# BMS_Master.net
KiCad netlist of a schematic drawn in EAGLE
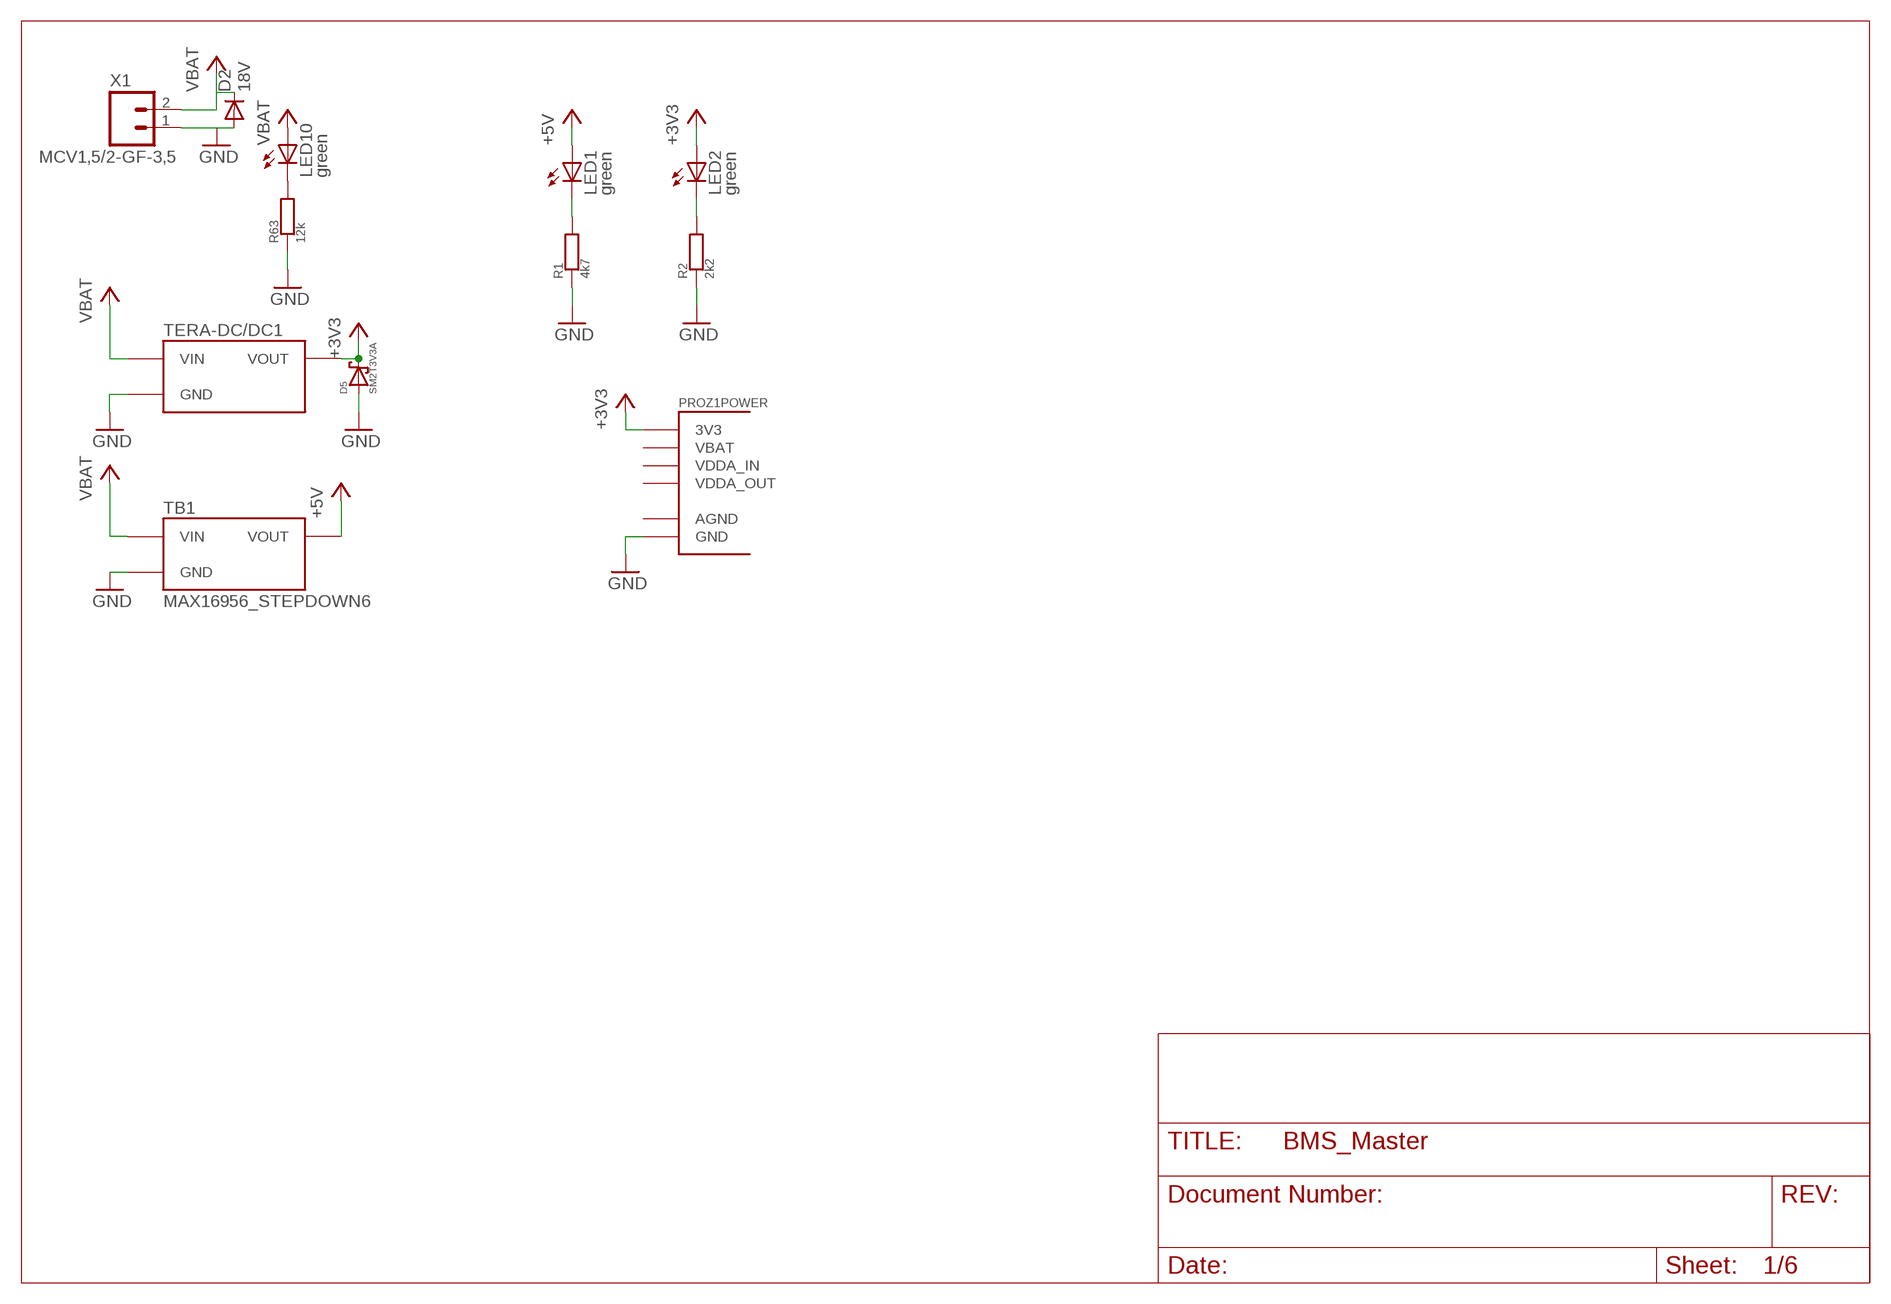
[diagram p0: schematic, sheet 1]
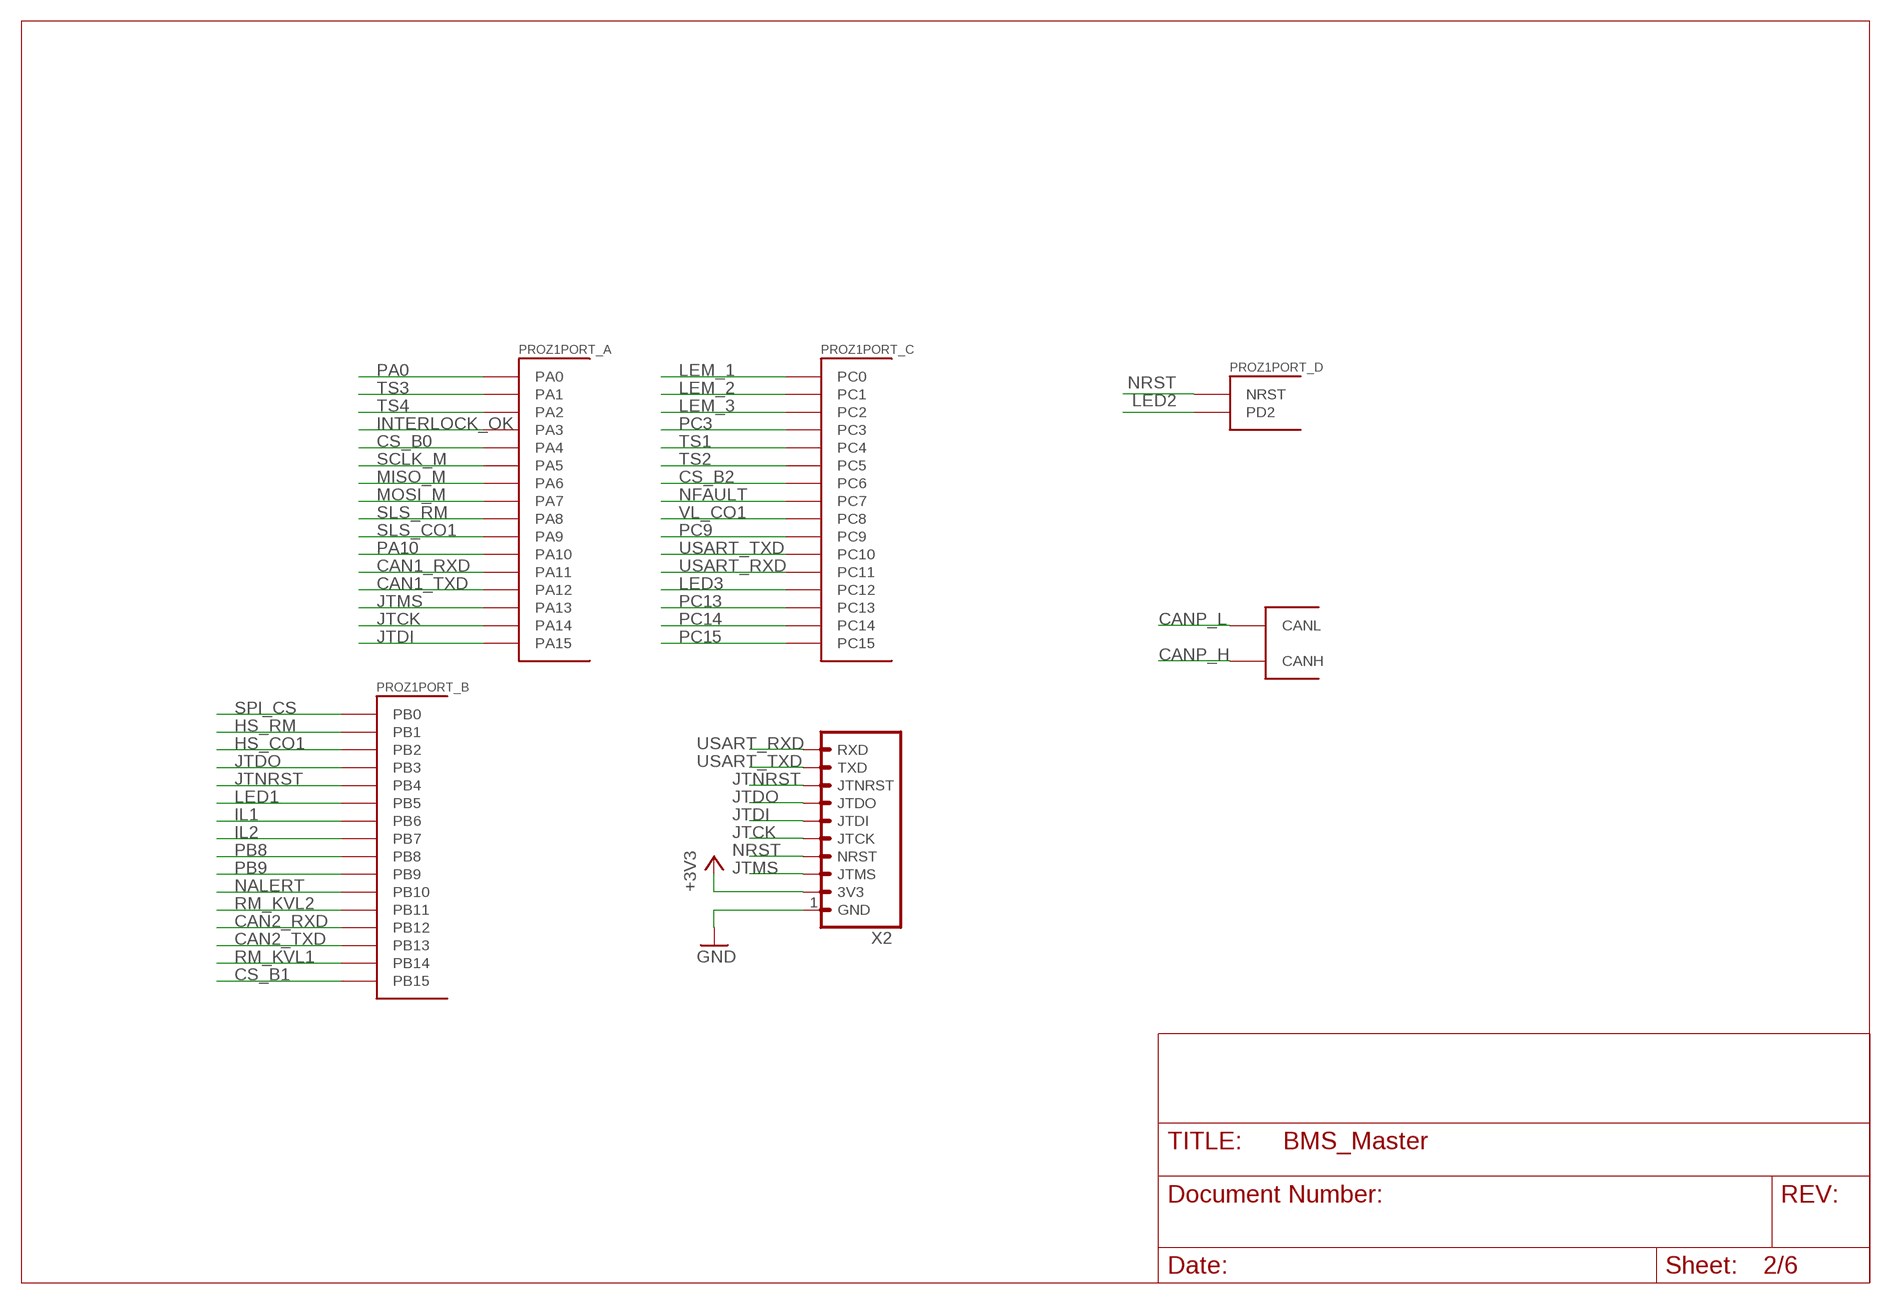
[diagram p1: schematic, sheet 2]
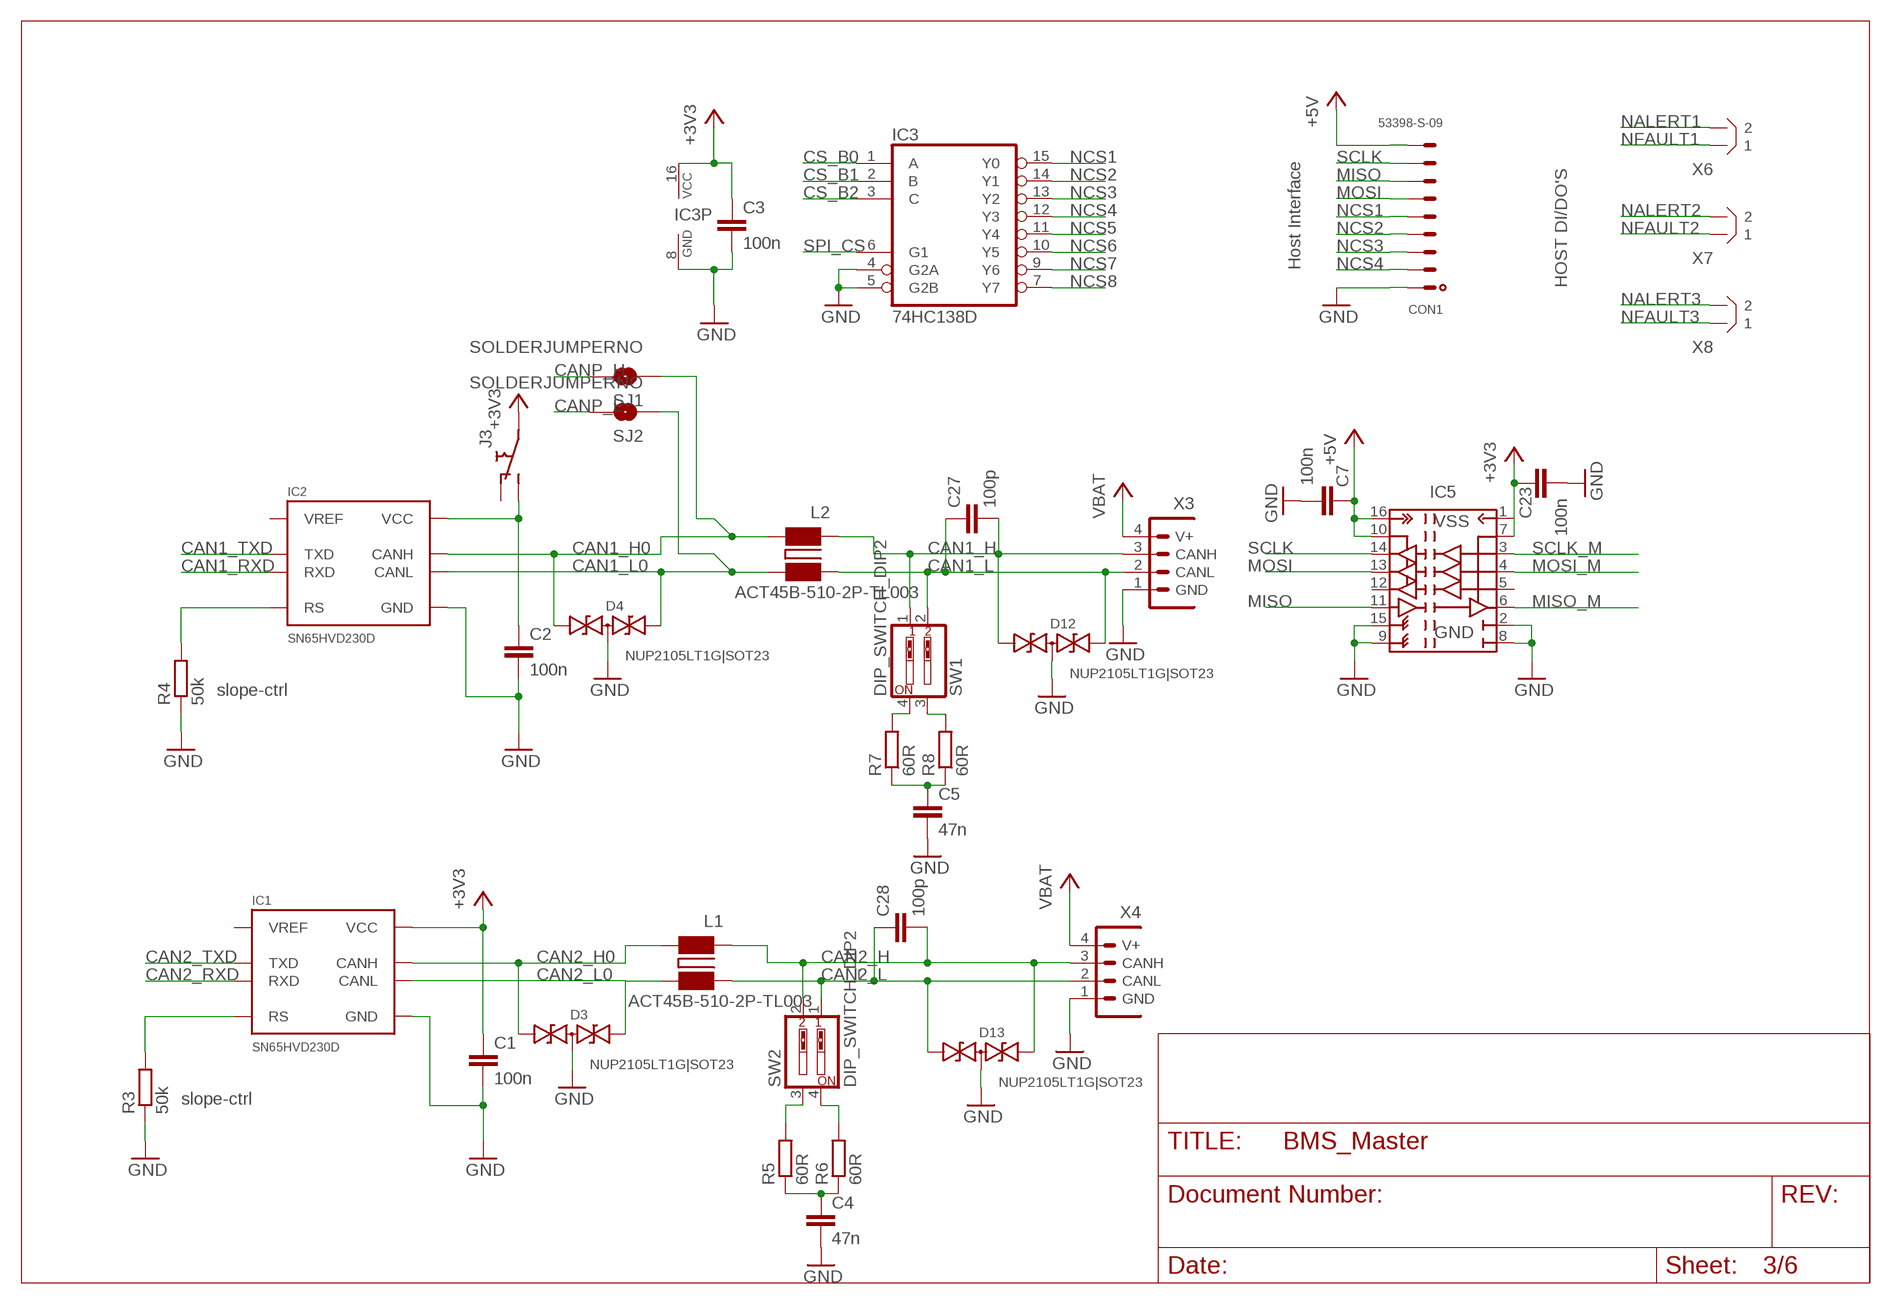
[diagram p2: schematic, sheet 3]
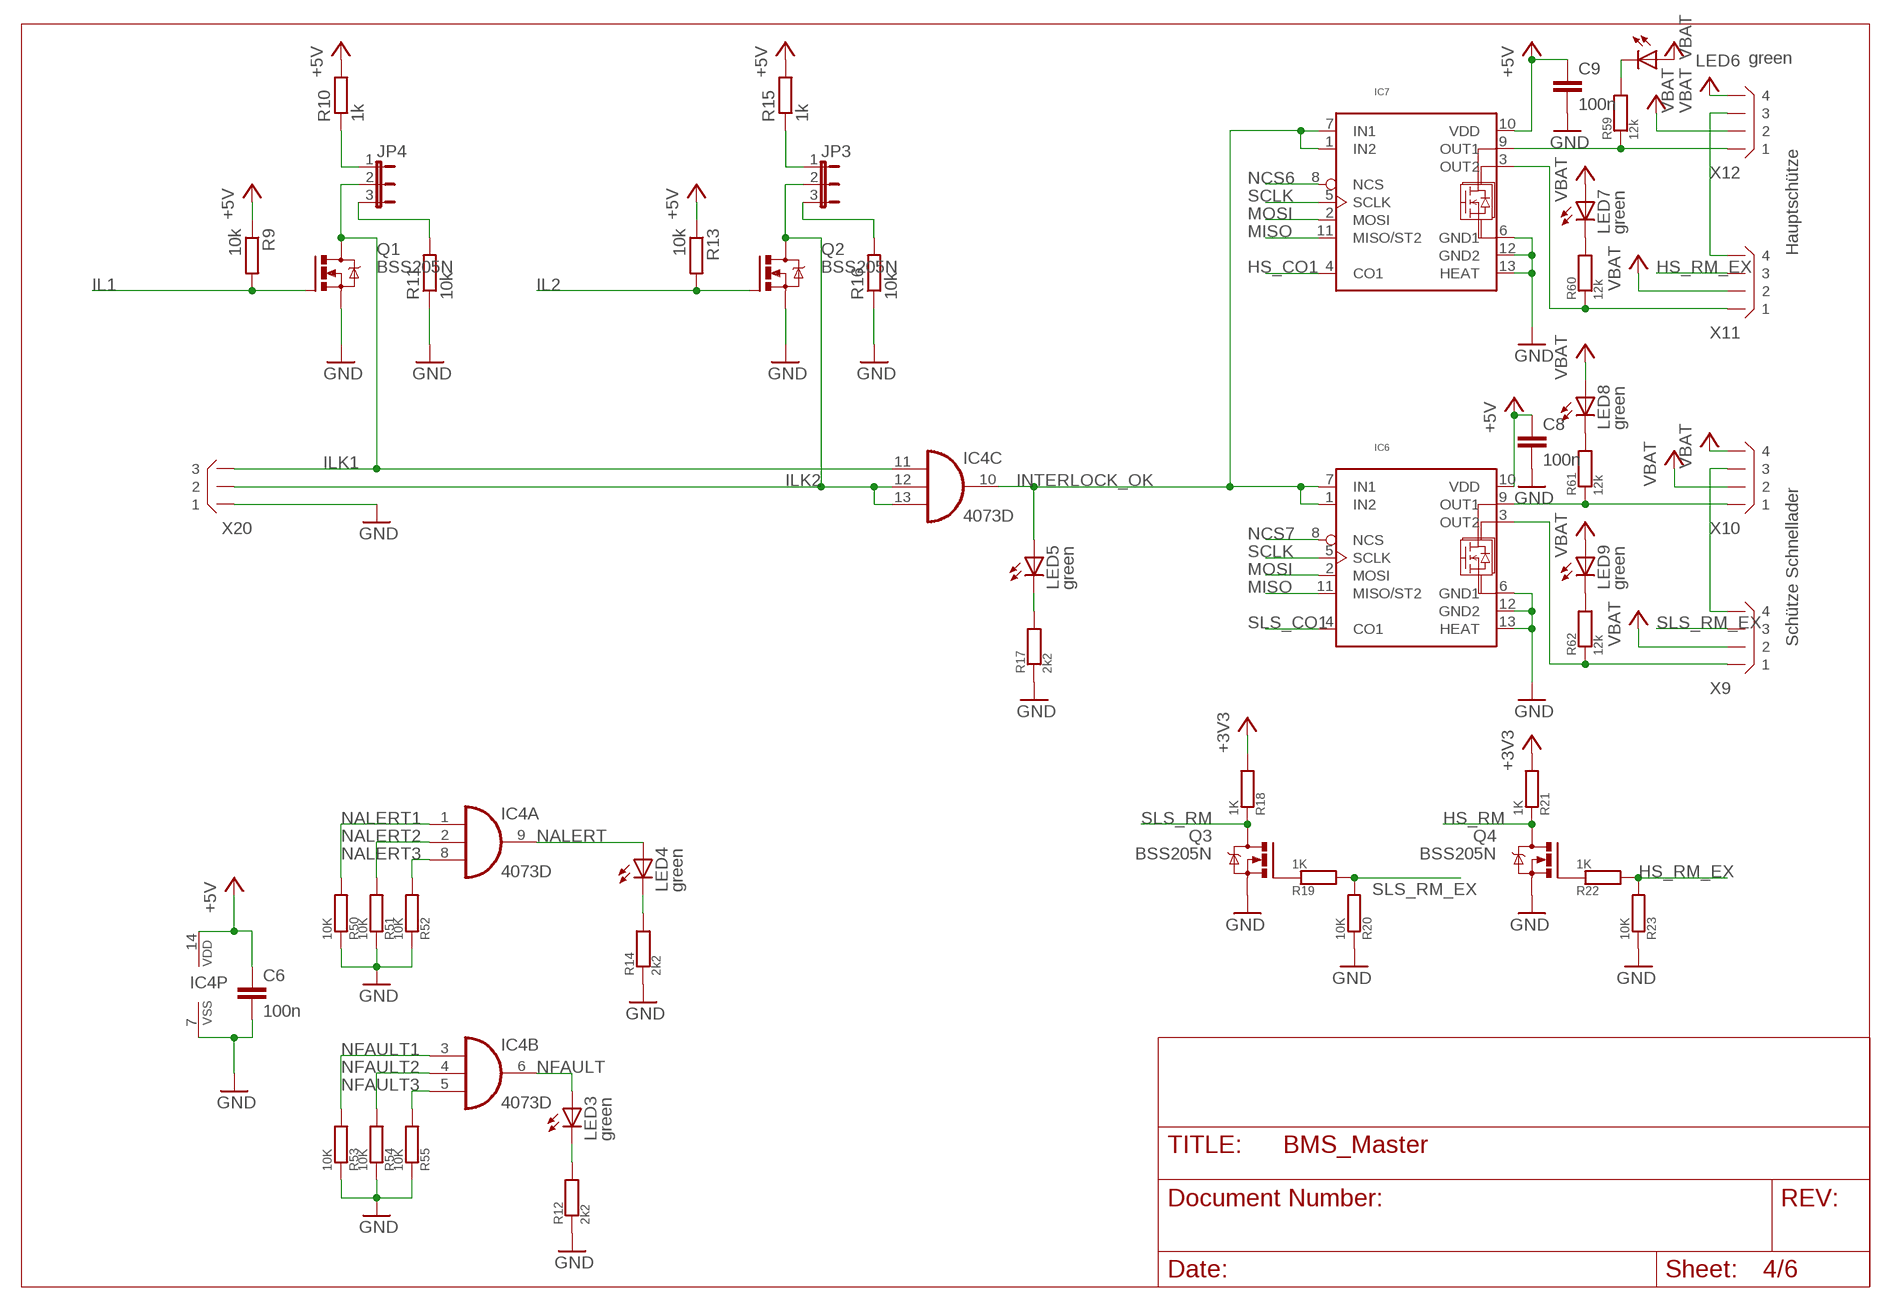
[diagram p3: schematic, sheet 4]
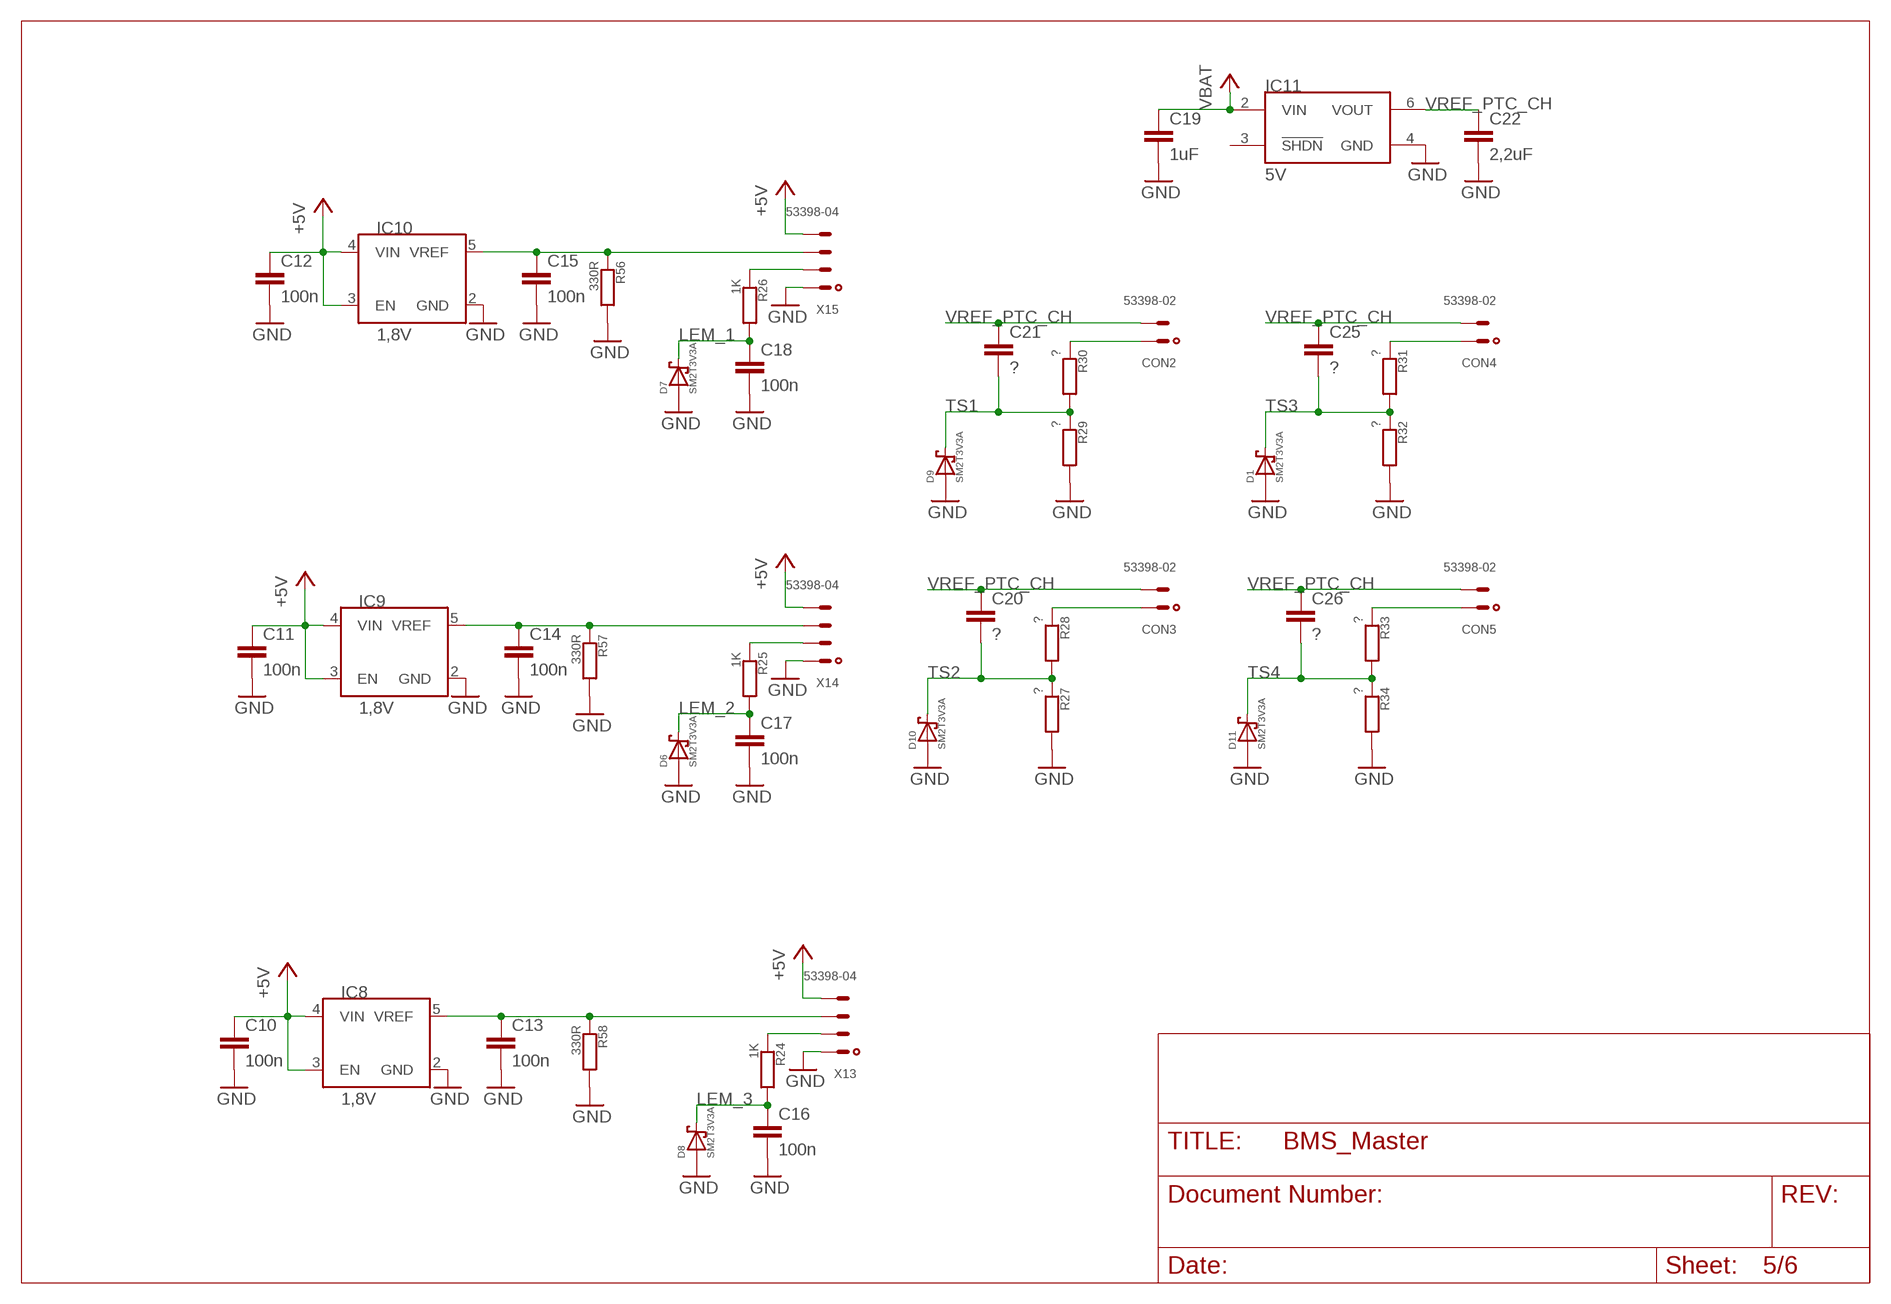
[diagram p4: schematic, sheet 5]
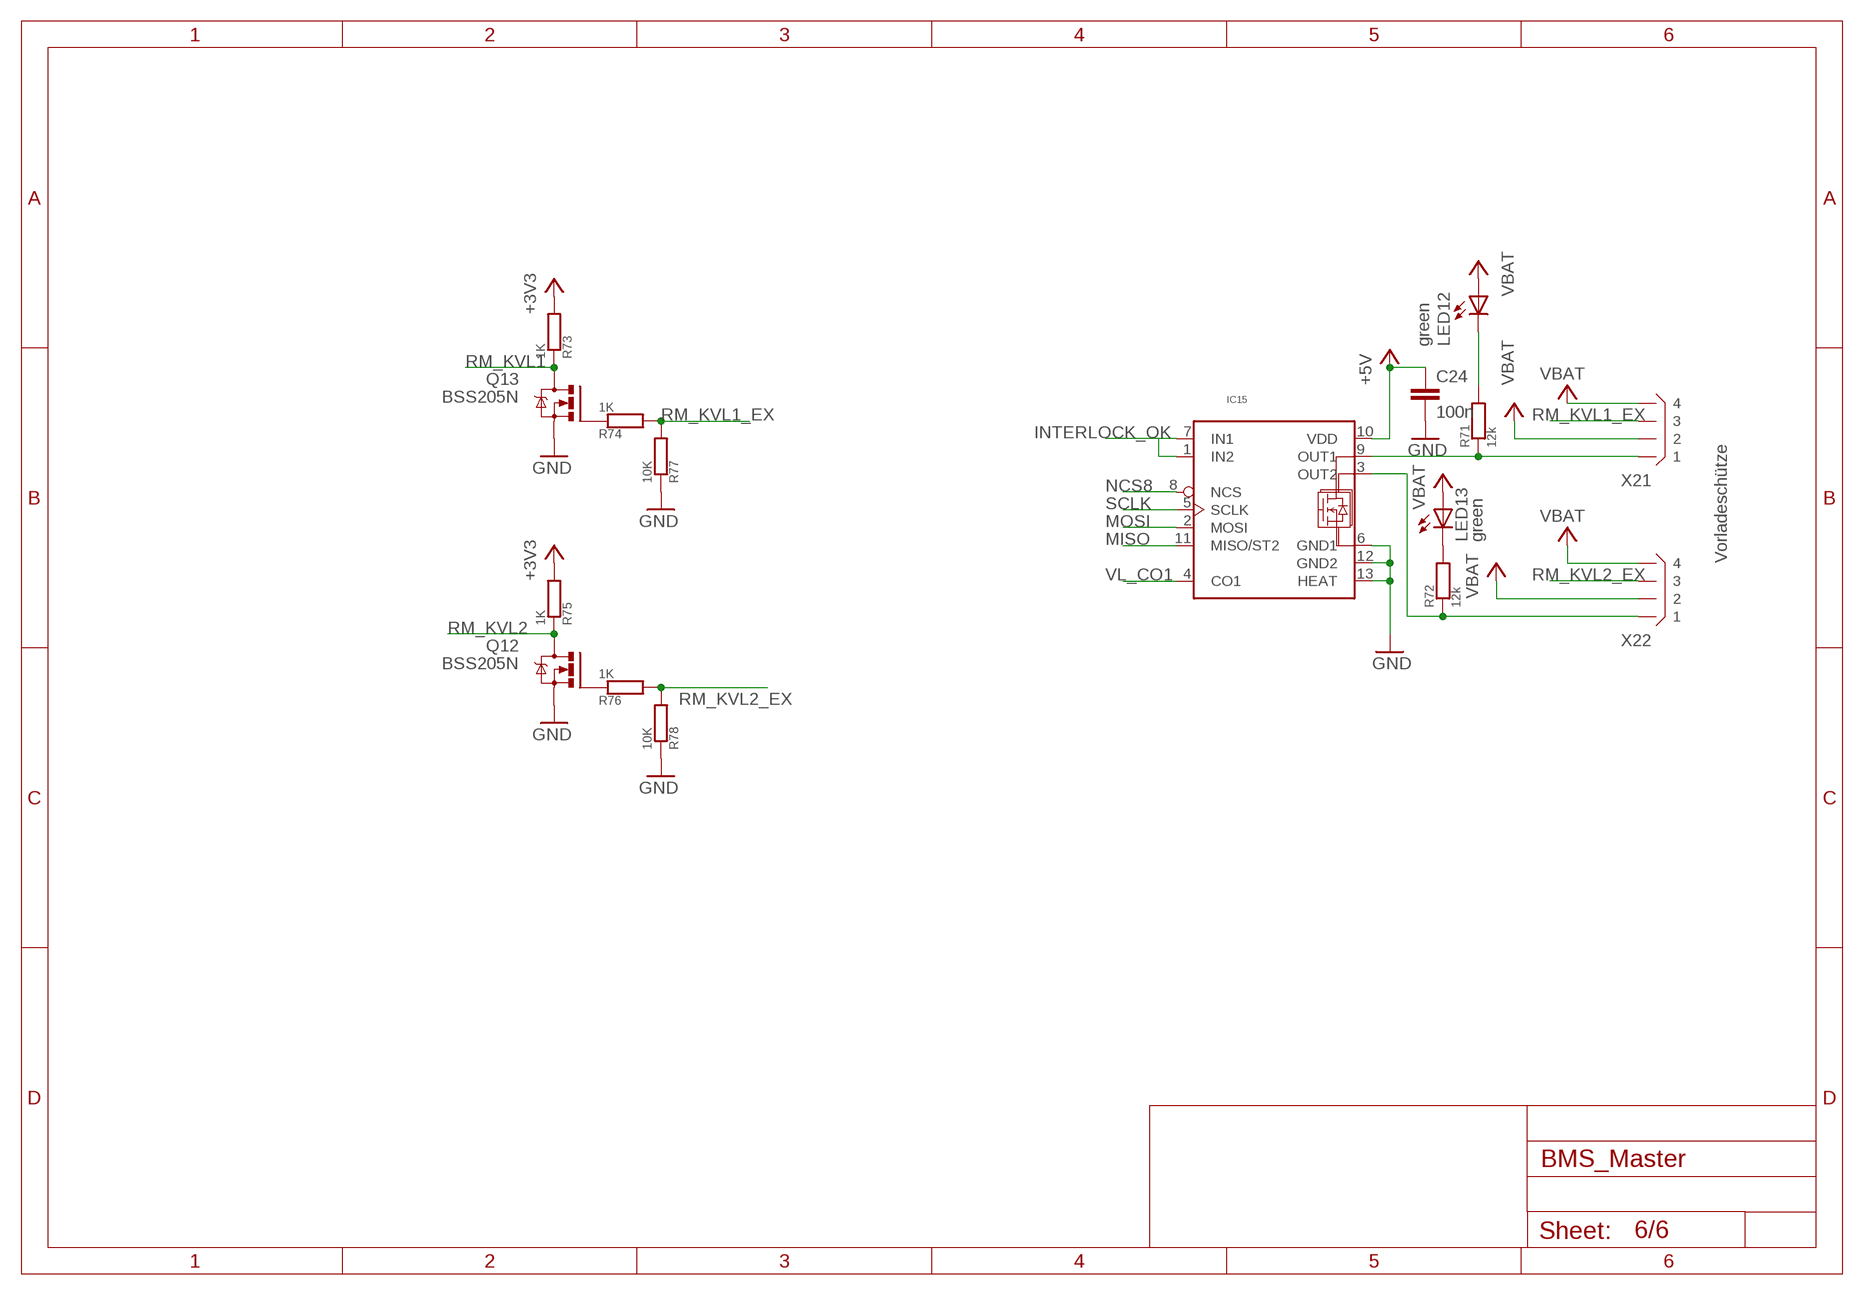
[diagram p5: schematic, sheet 6]

(export (version "E")
  (design (tool "Eeschema 10.0.6"))
  (components
    (comp (ref "PROZ1")
      (value "STM32F4_PROZESSORBOARDRPZ")
      (footprint "eagle-import:STM32F4_PROZESSORBOARD")
      (libsource (lib "eagle-import") (part "STM32F4_PROZESSORBOARDRPZ"))
    )
    (comp (ref "X2")
      (value "TERA-PROG-DEBUG-10GERADE")
      (footprint "eagle-import:90130-1110")
      (libsource (lib "eagle-import") (part "TERA-PROG-DEBUG-10GERADE"))
    )
    (comp (ref "D2")
      (value "18V")
      (footprint "eagle-import:DO214AA")
      (libsource (lib "eagle-import") (part "DIODE-DO214AA"))
    )
    (comp (ref "D5")
      (value "SM2T3V3A")
      (footprint "eagle-import:SM2T3V3A")
      (libsource (lib "eagle-import") (part "SM2T3V3A"))
    )
    (comp (ref "LED1")
      (value "green")
      (footprint "eagle-import:CHIP-LED0805")
      (libsource (lib "eagle-import") (part "LEDCHIP-LED0805"))
    )
    (comp (ref "LED2")
      (value "green")
      (footprint "eagle-import:CHIP-LED0805")
      (libsource (lib "eagle-import") (part "LEDCHIP-LED0805"))
    )
    (comp (ref "LED10")
      (value "green")
      (footprint "eagle-import:CHIP-LED0805")
      (libsource (lib "eagle-import") (part "LEDCHIP-LED0805"))
    )
    (comp (ref "R1")
      (value "4k7")
      (footprint "eagle-import:R0805")
      (libsource (lib "eagle-import") (part "R"))
    )
    (comp (ref "R2")
      (value "2k2")
      (footprint "eagle-import:R0805")
      (libsource (lib "eagle-import") (part "R"))
    )
    (comp (ref "R63")
      (value "12k")
      (footprint "eagle-import:R0805")
      (libsource (lib "eagle-import") (part "R"))
    )
    (comp (ref "TB1")
      (value "MAX16956_STEPDOWN6")
      (footprint "eagle-import:MAX16956_STEPDOWN6")
      (libsource (lib "eagle-import") (part "MAX16956_STEPDOWN6"))
    )
    (comp (ref "TERA-DC/DC1")
      (value "MAX5035_STEPDOWN3")
      (footprint "eagle-import:MAX5035_STEPDOWN3")
      (libsource (lib "eagle-import") (part "MAX5035_STEPDOWN3"))
    )
    (comp (ref "X1")
      (value "MCV1,5/2-GF-3,5")
      (footprint "eagle-import:MCV1,5_2-GF-3,5")
      (libsource (lib "eagle-import") (part "MCV1,5/2-GF-3,5"))
    )
    (comp (ref "C1")
      (value "100n")
      (footprint "eagle-import:C0805")
      (libsource (lib "eagle-import") (part "C-EUC0805"))
    )
    (comp (ref "C2")
      (value "100n")
      (footprint "eagle-import:C0805")
      (libsource (lib "eagle-import") (part "C-EUC0805"))
    )
    (comp (ref "C3")
      (value "100n")
      (footprint "eagle-import:C0805")
      (libsource (lib "eagle-import") (part "C-EUC0805"))
    )
    (comp (ref "C4")
      (value "47n")
      (footprint "eagle-import:C0603")
      (libsource (lib "eagle-import") (part "C-EUC0603"))
    )
    (comp (ref "C5")
      (value "47n")
      (footprint "eagle-import:C0603")
      (libsource (lib "eagle-import") (part "C-EUC0603"))
    )
    (comp (ref "C7")
      (value "100n")
      (footprint "eagle-import:C0603")
      (libsource (lib "eagle-import") (part "C0603"))
    )
    (comp (ref "C23")
      (value "100n")
      (footprint "eagle-import:C0603")
      (libsource (lib "eagle-import") (part "C0603"))
    )
    (comp (ref "C27")
      (value "100p")
      (footprint "eagle-import:C0603")
      (libsource (lib "eagle-import") (part "C-EUC0603"))
    )
    (comp (ref "C28")
      (value "100p")
      (footprint "eagle-import:C0603")
      (libsource (lib "eagle-import") (part "C-EUC0603"))
    )
    (comp (ref "CON1")
      (value "53398-S-09")
      (footprint "eagle-import:53398-09-S")
      (libsource (lib "eagle-import") (part "53?-09398-S"))
    )
    (comp (ref "D3")
      (value "NUP2105LT1G|SOT23")
      (footprint "eagle-import:SOT23")
      (libsource (lib "eagle-import") (part "NUP2105LT1G|SOT23"))
    )
    (comp (ref "D4")
      (value "NUP2105LT1G|SOT23")
      (footprint "eagle-import:SOT23")
      (libsource (lib "eagle-import") (part "NUP2105LT1G|SOT23"))
    )
    (comp (ref "D12")
      (value "NUP2105LT1G|SOT23")
      (footprint "eagle-import:SOT23")
      (libsource (lib "eagle-import") (part "NUP2105LT1G|SOT23"))
    )
    (comp (ref "D13")
      (value "NUP2105LT1G|SOT23")
      (footprint "eagle-import:SOT23")
      (libsource (lib "eagle-import") (part "NUP2105LT1G|SOT23"))
    )
    (comp (ref "IC1")
      (value "SN65HVD230D")
      (footprint "eagle-import:SO08")
      (libsource (lib "eagle-import") (part "SN65HVD23D0"))
    )
    (comp (ref "IC2")
      (value "SN65HVD230D")
      (footprint "eagle-import:SO08")
      (libsource (lib "eagle-import") (part "SN65HVD23D0"))
    )
    (comp (ref "IC3")
      (value "74HC138D")
      (footprint "eagle-import:SO16")
      (libsource (lib "eagle-import") (part "74138DHC"))
    )
    (comp (ref "IC5")
      (value "ISO7241")
      (footprint "eagle-import:R-PDSO-G16")
      (libsource (lib "eagle-import") (part "ISO7241"))
    )
    (comp (ref "J3")
      (value "JUMPER_SWITCHS")
      (footprint "eagle-import:J_OR_S")
      (libsource (lib "eagle-import") (part "JUMPER_SWITCHS"))
    )
    (comp (ref "L1")
      (value "ACT45B-510-2P-TL003")
      (footprint "eagle-import:ACT45B")
      (libsource (lib "eagle-import") (part "ACT45B-510-2P-TL003"))
    )
    (comp (ref "L2")
      (value "ACT45B-510-2P-TL003")
      (footprint "eagle-import:ACT45B")
      (libsource (lib "eagle-import") (part "ACT45B-510-2P-TL003"))
    )
    (comp (ref "R3")
      (value "50k")
      (footprint "eagle-import:R0805")
      (libsource (lib "eagle-import") (part "R-EU_R0805"))
    )
    (comp (ref "R4")
      (value "50k")
      (footprint "eagle-import:R0805")
      (libsource (lib "eagle-import") (part "R-EU_R0805"))
    )
    (comp (ref "R5")
      (value "60R")
      (footprint "eagle-import:R0603")
      (libsource (lib "eagle-import") (part "R-EU_R0603"))
    )
    (comp (ref "R6")
      (value "60R")
      (footprint "eagle-import:R0603")
      (libsource (lib "eagle-import") (part "R-EU_R0603"))
    )
    (comp (ref "R7")
      (value "60R")
      (footprint "eagle-import:R0603")
      (libsource (lib "eagle-import") (part "R-EU_R0603"))
    )
    (comp (ref "R8")
      (value "60R")
      (footprint "eagle-import:R0603")
      (libsource (lib "eagle-import") (part "R-EU_R0603"))
    )
    (comp (ref "SJ1")
      (value "SOLDERJUMPERNO")
      (footprint "eagle-import:SJ_2S-NO")
      (libsource (lib "eagle-import") (part "SOLDERJUMPERNO"))
    )
    (comp (ref "SJ2")
      (value "SOLDERJUMPERNO")
      (footprint "eagle-import:SJ_2S-NO")
      (libsource (lib "eagle-import") (part "SOLDERJUMPERNO"))
    )
    (comp (ref "SW1")
      (value "DIP_SWITCH_DIP2")
      (footprint "eagle-import:DIPSWITCH-02")
      (libsource (lib "eagle-import") (part "DIP_SWITCH_DIP2"))
    )
    (comp (ref "SW2")
      (value "DIP_SWITCH_DIP2")
      (footprint "eagle-import:DIPSWITCH-02")
      (libsource (lib "eagle-import") (part "DIP_SWITCH_DIP2"))
    )
    (comp (ref "X3")
      (value "CIOC_4-1-FV-A_CAN-BELEGUNG")
      (footprint "eagle-import:CIOC_4-1-FV")
      (libsource (lib "eagle-import") (part "CIOC_4-1-FV-A_CAN-BELEGUNG"))
    )
    (comp (ref "X4")
      (value "CIOC_4-1-FV-A_CAN-BELEGUNG")
      (footprint "eagle-import:CIOC_4-1-FV")
      (libsource (lib "eagle-import") (part "CIOC_4-1-FV-A_CAN-BELEGUNG"))
    )
    (comp (ref "X6")
      (value "B2B-XH")
      (footprint "eagle-import:B2B-XH")
      (libsource (lib "eagle-import") (part "?2B-XHB"))
    )
    (comp (ref "X7")
      (value "B2B-XH")
      (footprint "eagle-import:B2B-XH")
      (libsource (lib "eagle-import") (part "?2B-XHB"))
    )
    (comp (ref "X8")
      (value "B2B-XH")
      (footprint "eagle-import:B2B-XH")
      (libsource (lib "eagle-import") (part "?2B-XHB"))
    )
    (comp (ref "C6")
      (value "100n")
      (footprint "eagle-import:C0603")
      (libsource (lib "eagle-import") (part "C-EUC0603"))
    )
    (comp (ref "C8")
      (value "100n")
      (footprint "eagle-import:C0603")
      (libsource (lib "eagle-import") (part "C-EUC0603"))
    )
    (comp (ref "C9")
      (value "100n")
      (footprint "eagle-import:C0603")
      (libsource (lib "eagle-import") (part "C-EUC0603"))
    )
    (comp (ref "IC4")
      (value "4073D")
      (footprint "eagle-import:SO14")
      (libsource (lib "eagle-import") (part "4073D"))
    )
    (comp (ref "IC6")
      (value "TLE8102SGN")
      (footprint "eagle-import:INF-PG-DSO-12-11_N_1PRIMARY")
      (libsource (lib "eagle-import") (part "TLE8102SGN"))
    )
    (comp (ref "IC7")
      (value "TLE8102SGN")
      (footprint "eagle-import:INF-PG-DSO-12-11_N_1PRIMARY")
      (libsource (lib "eagle-import") (part "TLE8102SGN"))
    )
    (comp (ref "JP3")
      (value "JUMPER_OR")
      (footprint "eagle-import:JP2_OCT")
      (libsource (lib "eagle-import") (part "JUMPER_OR"))
    )
    (comp (ref "JP4")
      (value "JUMPER_OR")
      (footprint "eagle-import:JP2_OCT")
      (libsource (lib "eagle-import") (part "JUMPER_OR"))
    )
    (comp (ref "LED3")
      (value "green")
      (footprint "eagle-import:CHIPLED_0805")
      (libsource (lib "eagle-import") (part "LEDCHIPLED_0805"))
    )
    (comp (ref "LED4")
      (value "green")
      (footprint "eagle-import:CHIPLED_0805")
      (libsource (lib "eagle-import") (part "LEDCHIPLED_0805"))
    )
    (comp (ref "LED5")
      (value "green")
      (footprint "eagle-import:CHIPLED_0805")
      (libsource (lib "eagle-import") (part "LEDCHIPLED_0805"))
    )
    (comp (ref "LED6")
      (value "green")
      (footprint "eagle-import:CHIP-LED0805")
      (libsource (lib "eagle-import") (part "LEDCHIP-LED0805"))
    )
    (comp (ref "LED7")
      (value "green")
      (footprint "eagle-import:CHIP-LED0805")
      (libsource (lib "eagle-import") (part "LEDCHIP-LED0805"))
    )
    (comp (ref "LED8")
      (value "green")
      (footprint "eagle-import:CHIP-LED0805")
      (libsource (lib "eagle-import") (part "LEDCHIP-LED0805"))
    )
    (comp (ref "LED9")
      (value "green")
      (footprint "eagle-import:CHIP-LED0805")
      (libsource (lib "eagle-import") (part "LEDCHIP-LED0805"))
    )
    (comp (ref "Q1")
      (value "BSS205N")
      (footprint "eagle-import:SOT23")
      (libsource (lib "eagle-import") (part "BSS205N"))
    )
    (comp (ref "Q2")
      (value "BSS205N")
      (footprint "eagle-import:SOT23")
      (libsource (lib "eagle-import") (part "BSS205N"))
    )
    (comp (ref "Q3")
      (value "BSS205N")
      (footprint "eagle-import:SOT23")
      (libsource (lib "eagle-import") (part "BSS205N"))
    )
    (comp (ref "Q4")
      (value "BSS205N")
      (footprint "eagle-import:SOT23")
      (libsource (lib "eagle-import") (part "BSS205N"))
    )
    (comp (ref "R9")
      (value "10k")
      (footprint "eagle-import:R0603")
      (libsource (lib "eagle-import") (part "R-EU_R0603"))
    )
    (comp (ref "R10")
      (value "1k")
      (footprint "eagle-import:R0603")
      (libsource (lib "eagle-import") (part "R-EU_R0603"))
    )
    (comp (ref "R11")
      (value "10k")
      (footprint "eagle-import:R0603")
      (libsource (lib "eagle-import") (part "R-EU_R0603"))
    )
    (comp (ref "R12")
      (value "2k2")
      (footprint "eagle-import:R0805")
      (libsource (lib "eagle-import") (part "R"))
    )
    (comp (ref "R13")
      (value "10k")
      (footprint "eagle-import:R0603")
      (libsource (lib "eagle-import") (part "R-EU_R0603"))
    )
    (comp (ref "R14")
      (value "2k2")
      (footprint "eagle-import:R0805")
      (libsource (lib "eagle-import") (part "R"))
    )
    (comp (ref "R15")
      (value "1k")
      (footprint "eagle-import:R0603")
      (libsource (lib "eagle-import") (part "R-EU_R0603"))
    )
    (comp (ref "R16")
      (value "10k")
      (footprint "eagle-import:R0603")
      (libsource (lib "eagle-import") (part "R-EU_R0603"))
    )
    (comp (ref "R17")
      (value "2k2")
      (footprint "eagle-import:R0805")
      (libsource (lib "eagle-import") (part "R"))
    )
    (comp (ref "R18")
      (value "1K")
      (footprint "eagle-import:R0603")
      (libsource (lib "eagle-import") (part "R0603"))
    )
    (comp (ref "R19")
      (value "1K")
      (footprint "eagle-import:R0805")
      (libsource (lib "eagle-import") (part "R"))
    )
    (comp (ref "R20")
      (value "10K")
      (footprint "eagle-import:R0805")
      (libsource (lib "eagle-import") (part "R"))
    )
    (comp (ref "R21")
      (value "1K")
      (footprint "eagle-import:R0603")
      (libsource (lib "eagle-import") (part "R0603"))
    )
    (comp (ref "R22")
      (value "1K")
      (footprint "eagle-import:R0805")
      (libsource (lib "eagle-import") (part "R"))
    )
    (comp (ref "R23")
      (value "10K")
      (footprint "eagle-import:R0805")
      (libsource (lib "eagle-import") (part "R"))
    )
    (comp (ref "R50")
      (value "10K")
      (footprint "eagle-import:R0603")
      (libsource (lib "eagle-import") (part "R0603"))
    )
    (comp (ref "R51")
      (value "10K")
      (footprint "eagle-import:R0603")
      (libsource (lib "eagle-import") (part "R0603"))
    )
    (comp (ref "R52")
      (value "10K")
      (footprint "eagle-import:R0603")
      (libsource (lib "eagle-import") (part "R0603"))
    )
    (comp (ref "R53")
      (value "10K")
      (footprint "eagle-import:R0603")
      (libsource (lib "eagle-import") (part "R0603"))
    )
    (comp (ref "R54")
      (value "10K")
      (footprint "eagle-import:R0603")
      (libsource (lib "eagle-import") (part "R0603"))
    )
    (comp (ref "R55")
      (value "10K")
      (footprint "eagle-import:R0603")
      (libsource (lib "eagle-import") (part "R0603"))
    )
    (comp (ref "R59")
      (value "12k")
      (footprint "eagle-import:R0805")
      (libsource (lib "eagle-import") (part "R"))
    )
    (comp (ref "R60")
      (value "12k")
      (footprint "eagle-import:R0805")
      (libsource (lib "eagle-import") (part "R"))
    )
    (comp (ref "R61")
      (value "12k")
      (footprint "eagle-import:R0805")
      (libsource (lib "eagle-import") (part "R"))
    )
    (comp (ref "R62")
      (value "12k")
      (footprint "eagle-import:R0805")
      (libsource (lib "eagle-import") (part "R"))
    )
    (comp (ref "X9")
      (value "B4B-XH")
      (footprint "eagle-import:B4B-XH")
      (libsource (lib "eagle-import") (part "?4B-XHB"))
    )
    (comp (ref "X10")
      (value "B4B-XH")
      (footprint "eagle-import:B4B-XH")
      (libsource (lib "eagle-import") (part "?4B-XHB"))
    )
    (comp (ref "X11")
      (value "B4B-XH")
      (footprint "eagle-import:B4B-XH")
      (libsource (lib "eagle-import") (part "?4B-XHB"))
    )
    (comp (ref "X12")
      (value "B4B-XH")
      (footprint "eagle-import:B4B-XH")
      (libsource (lib "eagle-import") (part "?4B-XHB"))
    )
    (comp (ref "X20")
      (value "B3B-XH")
      (footprint "eagle-import:B3B-XH")
      (libsource (lib "eagle-import") (part "?3B-XHB"))
    )
    (comp (ref "C24")
      (value "100n")
      (footprint "eagle-import:C0603")
      (libsource (lib "eagle-import") (part "C-EUC0603"))
    )
    (comp (ref "IC15")
      (value "TLE8102SGN")
      (footprint "eagle-import:INF-PG-DSO-12-11_N_1PRIMARY")
      (libsource (lib "eagle-import") (part "TLE8102SGN"))
    )
    (comp (ref "LED12")
      (value "green")
      (footprint "eagle-import:CHIP-LED0805")
      (libsource (lib "eagle-import") (part "LEDCHIP-LED0805"))
    )
    (comp (ref "LED13")
      (value "green")
      (footprint "eagle-import:CHIP-LED0805")
      (libsource (lib "eagle-import") (part "LEDCHIP-LED0805"))
    )
    (comp (ref "Q12")
      (value "BSS205N")
      (footprint "eagle-import:SOT23")
      (libsource (lib "eagle-import") (part "BSS205N"))
    )
    (comp (ref "Q13")
      (value "BSS205N")
      (footprint "eagle-import:SOT23")
      (libsource (lib "eagle-import") (part "BSS205N"))
    )
    (comp (ref "R71")
      (value "12k")
      (footprint "eagle-import:R0805")
      (libsource (lib "eagle-import") (part "R"))
    )
    (comp (ref "R72")
      (value "12k")
      (footprint "eagle-import:R0805")
      (libsource (lib "eagle-import") (part "R"))
    )
    (comp (ref "R73")
      (value "1K")
      (footprint "eagle-import:R0805")
      (libsource (lib "eagle-import") (part "R"))
    )
    (comp (ref "R74")
      (value "1K")
      (footprint "eagle-import:R0805")
      (libsource (lib "eagle-import") (part "R"))
    )
    (comp (ref "R75")
      (value "1K")
      (footprint "eagle-import:R0805")
      (libsource (lib "eagle-import") (part "R"))
    )
    (comp (ref "R76")
      (value "1K")
      (footprint "eagle-import:R0805")
      (libsource (lib "eagle-import") (part "R"))
    )
    (comp (ref "R77")
      (value "10K")
      (footprint "eagle-import:R0805")
      (libsource (lib "eagle-import") (part "R"))
    )
    (comp (ref "R78")
      (value "10K")
      (footprint "eagle-import:R0805")
      (libsource (lib "eagle-import") (part "R"))
    )
    (comp (ref "X21")
      (value "B4B-XH")
      (footprint "eagle-import:B4B-XH")
      (libsource (lib "eagle-import") (part "?4B-XHB"))
    )
    (comp (ref "X22")
      (value "B4B-XH")
      (footprint "eagle-import:B4B-XH")
      (libsource (lib "eagle-import") (part "?4B-XHB"))
    )
    (comp (ref "C10")
      (value "100n")
      (footprint "eagle-import:C0805")
      (libsource (lib "eagle-import") (part "C-EUC0805"))
    )
    (comp (ref "C11")
      (value "100n")
      (footprint "eagle-import:C0805")
      (libsource (lib "eagle-import") (part "C-EUC0805"))
    )
    (comp (ref "C12")
      (value "100n")
      (footprint "eagle-import:C0805")
      (libsource (lib "eagle-import") (part "C-EUC0805"))
    )
    (comp (ref "C13")
      (value "100n")
      (footprint "eagle-import:C0805")
      (libsource (lib "eagle-import") (part "C-EUC0805"))
    )
    (comp (ref "C14")
      (value "100n")
      (footprint "eagle-import:C0805")
      (libsource (lib "eagle-import") (part "C-EUC0805"))
    )
    (comp (ref "C15")
      (value "100n")
      (footprint "eagle-import:C0805")
      (libsource (lib "eagle-import") (part "C-EUC0805"))
    )
    (comp (ref "C16")
      (value "100n")
      (footprint "eagle-import:C0805")
      (libsource (lib "eagle-import") (part "C-EUC0805"))
    )
    (comp (ref "C17")
      (value "100n")
      (footprint "eagle-import:C0805")
      (libsource (lib "eagle-import") (part "C-EUC0805"))
    )
    (comp (ref "C18")
      (value "100n")
      (footprint "eagle-import:C0805")
      (libsource (lib "eagle-import") (part "C-EUC0805"))
    )
    (comp (ref "C19")
      (value "1uF")
      (footprint "eagle-import:C0805")
      (libsource (lib "eagle-import") (part "C-EUC0805"))
    )
    (comp (ref "C20")
      (value "?")
      (footprint "eagle-import:C0603")
      (libsource (lib "eagle-import") (part "C-EUC0603"))
    )
    (comp (ref "C21")
      (value "?")
      (footprint "eagle-import:C0603")
      (libsource (lib "eagle-import") (part "C-EUC0603"))
    )
    (comp (ref "C22")
      (value "2,2uF")
      (footprint "eagle-import:C0805")
      (libsource (lib "eagle-import") (part "C-EUC0805"))
    )
    (comp (ref "C25")
      (value "?")
      (footprint "eagle-import:C0603")
      (libsource (lib "eagle-import") (part "C-EUC0603"))
    )
    (comp (ref "C26")
      (value "?")
      (footprint "eagle-import:C0603")
      (libsource (lib "eagle-import") (part "C-EUC0603"))
    )
    (comp (ref "CON2")
      (value "53398-02")
      (footprint "eagle-import:53398-02")
      (libsource (lib "eagle-import") (part "53?-02398"))
    )
    (comp (ref "CON3")
      (value "53398-02")
      (footprint "eagle-import:53398-02")
      (libsource (lib "eagle-import") (part "53?-02398"))
    )
    (comp (ref "CON4")
      (value "53398-02")
      (footprint "eagle-import:53398-02")
      (libsource (lib "eagle-import") (part "53?-02398"))
    )
    (comp (ref "CON5")
      (value "53398-02")
      (footprint "eagle-import:53398-02")
      (libsource (lib "eagle-import") (part "53?-02398"))
    )
    (comp (ref "D1")
      (value "SM2T3V3A")
      (footprint "eagle-import:SM2T3V3A")
      (libsource (lib "eagle-import") (part "SM2T3V3A"))
    )
    (comp (ref "D6")
      (value "SM2T3V3A")
      (footprint "eagle-import:SM2T3V3A")
      (libsource (lib "eagle-import") (part "SM2T3V3A"))
    )
    (comp (ref "D7")
      (value "SM2T3V3A")
      (footprint "eagle-import:SM2T3V3A")
      (libsource (lib "eagle-import") (part "SM2T3V3A"))
    )
    (comp (ref "D8")
      (value "SM2T3V3A")
      (footprint "eagle-import:SM2T3V3A")
      (libsource (lib "eagle-import") (part "SM2T3V3A"))
    )
    (comp (ref "D9")
      (value "SM2T3V3A")
      (footprint "eagle-import:SM2T3V3A")
      (libsource (lib "eagle-import") (part "SM2T3V3A"))
    )
    (comp (ref "D10")
      (value "SM2T3V3A")
      (footprint "eagle-import:SM2T3V3A")
      (libsource (lib "eagle-import") (part "SM2T3V3A"))
    )
    (comp (ref "D11")
      (value "SM2T3V3A")
      (footprint "eagle-import:SM2T3V3A")
      (libsource (lib "eagle-import") (part "SM2T3V3A"))
    )
    (comp (ref "IC8")
      (value "1,8V")
      (footprint "eagle-import:SOT23-5L")
      (libsource (lib "eagle-import") (part "LM4132L"))
    )
    (comp (ref "IC9")
      (value "1,8V")
      (footprint "eagle-import:SOT23-5L")
      (libsource (lib "eagle-import") (part "LM4132L"))
    )
    (comp (ref "IC10")
      (value "1,8V")
      (footprint "eagle-import:SOT23-5L")
      (libsource (lib "eagle-import") (part "LM4132L"))
    )
    (comp (ref "IC11")
      (value "5V")
      (footprint "eagle-import:SO08")
      (libsource (lib "eagle-import") (part "LT1461"))
    )
    (comp (ref "R24")
      (value "1K")
      (footprint "eagle-import:R0805")
      (libsource (lib "eagle-import") (part "R"))
    )
    (comp (ref "R25")
      (value "1K")
      (footprint "eagle-import:R0805")
      (libsource (lib "eagle-import") (part "R"))
    )
    (comp (ref "R26")
      (value "1K")
      (footprint "eagle-import:R0805")
      (libsource (lib "eagle-import") (part "R"))
    )
    (comp (ref "R27")
      (value "?")
      (footprint "eagle-import:R0603")
      (libsource (lib "eagle-import") (part "R0603"))
    )
    (comp (ref "R28")
      (value "?")
      (footprint "eagle-import:R0603")
      (libsource (lib "eagle-import") (part "R0603"))
    )
    (comp (ref "R29")
      (value "?")
      (footprint "eagle-import:R0603")
      (libsource (lib "eagle-import") (part "R0603"))
    )
    (comp (ref "R30")
      (value "?")
      (footprint "eagle-import:R0603")
      (libsource (lib "eagle-import") (part "R0603"))
    )
    (comp (ref "R31")
      (value "?")
      (footprint "eagle-import:R0603")
      (libsource (lib "eagle-import") (part "R0603"))
    )
    (comp (ref "R32")
      (value "?")
      (footprint "eagle-import:R0603")
      (libsource (lib "eagle-import") (part "R0603"))
    )
    (comp (ref "R33")
      (value "?")
      (footprint "eagle-import:R0603")
      (libsource (lib "eagle-import") (part "R0603"))
    )
    (comp (ref "R34")
      (value "?")
      (footprint "eagle-import:R0603")
      (libsource (lib "eagle-import") (part "R0603"))
    )
    (comp (ref "R56")
      (value "330R")
      (footprint "eagle-import:R0805")
      (libsource (lib "eagle-import") (part "R"))
    )
    (comp (ref "R57")
      (value "330R")
      (footprint "eagle-import:R0805")
      (libsource (lib "eagle-import") (part "R"))
    )
    (comp (ref "R58")
      (value "330R")
      (footprint "eagle-import:R0805")
      (libsource (lib "eagle-import") (part "R"))
    )
    (comp (ref "X13")
      (value "53398-04")
      (footprint "eagle-import:53398-04")
      (libsource (lib "eagle-import") (part "53?-04398"))
    )
    (comp (ref "X14")
      (value "53398-04")
      (footprint "eagle-import:53398-04")
      (libsource (lib "eagle-import") (part "53?-04398"))
    )
    (comp (ref "X15")
      (value "53398-04")
      (footprint "eagle-import:53398-04")
      (libsource (lib "eagle-import") (part "53?-04398"))
    )
  )
  (nets
    (net (code "1") (name "+3V3") (class "Default")
      (node (ref "C1") (pin "1") (pinfunction "1_1") (pintype "passive"))
      (node (ref "C23") (pin "2") (pinfunction "2_2") (pintype "passive"))
      (node (ref "C3") (pin "1") (pinfunction "1_1") (pintype "passive"))
      (node (ref "D5") (pin "P$2") (pinfunction "P$2_P$2") (pintype "bidirectional"))
      (node (ref "IC1") (pin "3") (pinfunction "VCC_3") (pintype "power_in"))
      (node (ref "IC3") (pin "16") (pinfunction "VCC_16") (pintype "power_in"))
      (node (ref "IC5") (pin "1") (pinfunction "VCC1_1") (pintype "bidirectional"))
      (node (ref "IC5") (pin "7") (pinfunction "EN1_7") (pintype "bidirectional"))
      (node (ref "J3") (pin "P$1") (pinfunction "P$1_P$1") (pintype "bidirectional"))
      (node (ref "LED2") (pin "A") (pinfunction "A_A") (pintype "passive"))
      (node (ref "PROZ1") (pin "45") (pinfunction "3V3_45") (pintype "passive"))
      (node (ref "PROZ1") (pin "46") (pinfunction "3V3_46") (pintype "passive"))
      (node (ref "R18") (pin "2") (pinfunction "2_2") (pintype "passive"))
      (node (ref "R21") (pin "2") (pinfunction "2_2") (pintype "passive"))
      (node (ref "R73") (pin "2") (pinfunction "2_2") (pintype "passive"))
      (node (ref "R75") (pin "2") (pinfunction "2_2") (pintype "passive"))
      (node (ref "TERA-DC/DC1") (pin "VOUT") (pinfunction "VOUT_VOUT") (pintype "passive"))
      (node (ref "X2") (pin "2") (pinfunction "3V3_2") (pintype "passive"))
    )
    (net (code "2") (name "+5V") (class "Default")
      (node (ref "C10") (pin "1") (pinfunction "1_1") (pintype "passive"))
      (node (ref "C11") (pin "1") (pinfunction "1_1") (pintype "passive"))
      (node (ref "C12") (pin "1") (pinfunction "1_1") (pintype "passive"))
      (node (ref "C24") (pin "1") (pinfunction "1_1") (pintype "passive"))
      (node (ref "C6") (pin "1") (pinfunction "1_1") (pintype "passive"))
      (node (ref "C7") (pin "2") (pinfunction "2_2") (pintype "passive"))
      (node (ref "C8") (pin "1") (pinfunction "1_1") (pintype "passive"))
      (node (ref "C9") (pin "1") (pinfunction "1_1") (pintype "passive"))
      (node (ref "CON1") (pin "9") (pinfunction "9_9") (pintype "passive"))
      (node (ref "IC10") (pin "3") (pinfunction "EN_3") (pintype "bidirectional"))
      (node (ref "IC10") (pin "4") (pinfunction "VIN_4") (pintype "bidirectional"))
      (node (ref "IC15") (pin "10") (pinfunction "VDD_10") (pintype "bidirectional"))
      (node (ref "IC4") (pin "14") (pinfunction "VDD_14") (pintype "power_in"))
      (node (ref "IC5") (pin "10") (pinfunction "EN2_10") (pintype "bidirectional"))
      (node (ref "IC5") (pin "16") (pinfunction "VCC2_16") (pintype "bidirectional"))
      (node (ref "IC6") (pin "10") (pinfunction "VDD_10") (pintype "bidirectional"))
      (node (ref "IC7") (pin "10") (pinfunction "VDD_10") (pintype "bidirectional"))
      (node (ref "IC8") (pin "3") (pinfunction "EN_3") (pintype "bidirectional"))
      (node (ref "IC8") (pin "4") (pinfunction "VIN_4") (pintype "bidirectional"))
      (node (ref "IC9") (pin "3") (pinfunction "EN_3") (pintype "bidirectional"))
      (node (ref "IC9") (pin "4") (pinfunction "VIN_4") (pintype "bidirectional"))
      (node (ref "LED1") (pin "A") (pinfunction "A_A") (pintype "passive"))
      (node (ref "R10") (pin "2") (pinfunction "2_2") (pintype "passive"))
      (node (ref "R13") (pin "1") (pinfunction "1_1") (pintype "passive"))
      (node (ref "R15") (pin "2") (pinfunction "2_2") (pintype "passive"))
      (node (ref "R9") (pin "1") (pinfunction "1_1") (pintype "passive"))
      (node (ref "TB1") (pin "VOUT") (pinfunction "VOUT_VOUT") (pintype "passive"))
      (node (ref "X13") (pin "4") (pinfunction "4_4") (pintype "passive"))
      (node (ref "X14") (pin "4") (pinfunction "4_4") (pintype "passive"))
      (node (ref "X15") (pin "4") (pinfunction "4_4") (pintype "passive"))
    )
    (net (code "3") (name "CAN1_H") (class "Default")
      (node (ref "C27") (pin "2") (pinfunction "2_2") (pintype "passive"))
      (node (ref "D12") (pin "1") (pinfunction "P$1_1") (pintype "passive"))
      (node (ref "L2") (pin "P$3") (pinfunction "3_P$3") (pintype "passive"))
      (node (ref "SW1") (pin "1") (pinfunction "1_1") (pintype "passive"))
      (node (ref "X3") (pin "3") (pinfunction "CANH_3") (pintype "passive"))
    )
    (net (code "4") (name "CAN1_H0") (class "Default")
      (node (ref "D4") (pin "1") (pinfunction "P$1_1") (pintype "passive"))
      (node (ref "IC2") (pin "7") (pinfunction "CANH_7") (pintype "bidirectional"))
      (node (ref "L2") (pin "P$4") (pinfunction "4_P$4") (pintype "passive"))
      (node (ref "SJ1") (pin "1") (pinfunction "1_1") (pintype "passive"))
    )
    (net (code "5") (name "CAN1_L") (class "Default")
      (node (ref "C27") (pin "1") (pinfunction "1_1") (pintype "passive"))
      (node (ref "D12") (pin "2") (pinfunction "P$2_2") (pintype "passive"))
      (node (ref "L2") (pin "P$1") (pinfunction "1_P$1") (pintype "passive"))
      (node (ref "SW1") (pin "2") (pinfunction "2_2") (pintype "passive"))
      (node (ref "X3") (pin "2") (pinfunction "CANL_2") (pintype "passive"))
    )
    (net (code "6") (name "CAN1_L0") (class "Default")
      (node (ref "D4") (pin "2") (pinfunction "P$2_2") (pintype "passive"))
      (node (ref "IC2") (pin "6") (pinfunction "CANL_6") (pintype "bidirectional"))
      (node (ref "L2") (pin "P$2") (pinfunction "2_P$2") (pintype "passive"))
      (node (ref "SJ2") (pin "1") (pinfunction "1_1") (pintype "passive"))
    )
    (net (code "7") (name "CAN1_RXD") (class "Default")
      (node (ref "IC2") (pin "4") (pinfunction "RXD_4") (pintype "output"))
      (node (ref "PROZ1") (pin "26") (pinfunction "PA11_26") (pintype "bidirectional"))
    )
    (net (code "8") (name "CAN1_TXD") (class "Default")
      (node (ref "IC2") (pin "1") (pinfunction "TXD_1") (pintype "input"))
      (node (ref "PROZ1") (pin "24") (pinfunction "PA12_24") (pintype "bidirectional"))
    )
    (net (code "9") (name "CAN2_H") (class "Default")
      (node (ref "C28") (pin "2") (pinfunction "2_2") (pintype "passive"))
      (node (ref "D13") (pin "2") (pinfunction "P$2_2") (pintype "passive"))
      (node (ref "L1") (pin "P$3") (pinfunction "3_P$3") (pintype "passive"))
      (node (ref "SW2") (pin "2") (pinfunction "2_2") (pintype "passive"))
      (node (ref "X4") (pin "3") (pinfunction "CANH_3") (pintype "passive"))
    )
    (net (code "10") (name "CAN2_H0") (class "Default")
      (node (ref "D3") (pin "1") (pinfunction "P$1_1") (pintype "passive"))
      (node (ref "IC1") (pin "7") (pinfunction "CANH_7") (pintype "bidirectional"))
      (node (ref "L1") (pin "P$4") (pinfunction "4_P$4") (pintype "passive"))
    )
    (net (code "11") (name "CAN2_L") (class "Default")
      (node (ref "C28") (pin "1") (pinfunction "1_1") (pintype "passive"))
      (node (ref "D13") (pin "1") (pinfunction "P$1_1") (pintype "passive"))
      (node (ref "L1") (pin "P$1") (pinfunction "1_P$1") (pintype "passive"))
      (node (ref "SW2") (pin "1") (pinfunction "1_1") (pintype "passive"))
      (node (ref "X4") (pin "2") (pinfunction "CANL_2") (pintype "passive"))
    )
    (net (code "12") (name "CAN2_L0") (class "Default")
      (node (ref "D3") (pin "2") (pinfunction "P$2_2") (pintype "passive"))
      (node (ref "IC1") (pin "6") (pinfunction "CANL_6") (pintype "bidirectional"))
      (node (ref "L1") (pin "P$2") (pinfunction "2_P$2") (pintype "passive"))
    )
    (net (code "13") (name "CAN2_RXD") (class "Default")
      (node (ref "IC1") (pin "4") (pinfunction "RXD_4") (pintype "output"))
      (node (ref "PROZ1") (pin "50") (pinfunction "PB12_50") (pintype "bidirectional"))
    )
    (net (code "14") (name "CAN2_TXD") (class "Default")
      (node (ref "IC1") (pin "1") (pinfunction "TXD_1") (pintype "input"))
      (node (ref "PROZ1") (pin "49") (pinfunction "PB13_49") (pintype "bidirectional"))
    )
    (net (code "15") (name "CANP_H") (class "Default")
      (node (ref "PROZ1") (pin "31") (pinfunction "CANH_31") (pintype "bidirectional"))
      (node (ref "SJ1") (pin "2") (pinfunction "2_2") (pintype "passive"))
    )
    (net (code "16") (name "CANP_L") (class "Default")
      (node (ref "PROZ1") (pin "32") (pinfunction "CANL_32") (pintype "bidirectional"))
      (node (ref "SJ2") (pin "2") (pinfunction "2_2") (pintype "passive"))
    )
    (net (code "17") (name "CS_B0") (class "Default")
      (node (ref "IC3") (pin "1") (pinfunction "A_1") (pintype "input"))
      (node (ref "PROZ1") (pin "43") (pinfunction "PA4_43") (pintype "bidirectional"))
    )
    (net (code "18") (name "CS_B1") (class "Default")
      (node (ref "IC3") (pin "2") (pinfunction "B_2") (pintype "input"))
      (node (ref "PROZ1") (pin "51") (pinfunction "PB15_51") (pintype "bidirectional"))
    )
    (net (code "19") (name "CS_B2") (class "Default")
      (node (ref "IC3") (pin "3") (pinfunction "C_3") (pintype "input"))
      (node (ref "PROZ1") (pin "52") (pinfunction "PC6_52") (pintype "bidirectional"))
    )
    (net (code "20") (name "GND") (class "Default")
      (node (ref "C1") (pin "2") (pinfunction "2_2") (pintype "passive"))
      (node (ref "C10") (pin "2") (pinfunction "2_2") (pintype "passive"))
      (node (ref "C11") (pin "2") (pinfunction "2_2") (pintype "passive"))
      (node (ref "C12") (pin "2") (pinfunction "2_2") (pintype "passive"))
      (node (ref "C13") (pin "2") (pinfunction "2_2") (pintype "passive"))
      (node (ref "C14") (pin "2") (pinfunction "2_2") (pintype "passive"))
      (node (ref "C15") (pin "2") (pinfunction "2_2") (pintype "passive"))
      (node (ref "C16") (pin "2") (pinfunction "2_2") (pintype "passive"))
      (node (ref "C17") (pin "2") (pinfunction "2_2") (pintype "passive"))
      (node (ref "C18") (pin "2") (pinfunction "2_2") (pintype "passive"))
      (node (ref "C19") (pin "2") (pinfunction "2_2") (pintype "passive"))
      (node (ref "C2") (pin "2") (pinfunction "2_2") (pintype "passive"))
      (node (ref "C22") (pin "2") (pinfunction "2_2") (pintype "passive"))
      (node (ref "C23") (pin "1") (pinfunction "1_1") (pintype "passive"))
      (node (ref "C24") (pin "2") (pinfunction "2_2") (pintype "passive"))
      (node (ref "C3") (pin "2") (pinfunction "2_2") (pintype "passive"))
      (node (ref "C4") (pin "2") (pinfunction "2_2") (pintype "passive"))
      (node (ref "C5") (pin "2") (pinfunction "2_2") (pintype "passive"))
      (node (ref "C6") (pin "2") (pinfunction "2_2") (pintype "passive"))
      (node (ref "C7") (pin "1") (pinfunction "1_1") (pintype "passive"))
      (node (ref "C8") (pin "2") (pinfunction "2_2") (pintype "passive"))
      (node (ref "C9") (pin "2") (pinfunction "2_2") (pintype "passive"))
      (node (ref "CON1") (pin "1") (pinfunction "1_1") (pintype "passive"))
      (node (ref "D1") (pin "P$1") (pinfunction "P$1_P$1") (pintype "bidirectional"))
      (node (ref "D1") (pin "P$11") (pinfunction "P$1_P$11") (pintype "bidirectional"))
      (node (ref "D10") (pin "P$1") (pinfunction "P$1_P$1") (pintype "bidirectional"))
      (node (ref "D10") (pin "P$11") (pinfunction "P$1_P$11") (pintype "bidirectional"))
      (node (ref "D11") (pin "P$1") (pinfunction "P$1_P$1") (pintype "bidirectional"))
      (node (ref "D11") (pin "P$11") (pinfunction "P$1_P$11") (pintype "bidirectional"))
      (node (ref "D12") (pin "3") (pinfunction "P$3_3") (pintype "passive"))
      (node (ref "D13") (pin "3") (pinfunction "P$3_3") (pintype "passive"))
      (node (ref "D2") (pin "A") (pinfunction "A_A") (pintype "passive"))
      (node (ref "D3") (pin "3") (pinfunction "P$3_3") (pintype "passive"))
      (node (ref "D4") (pin "3") (pinfunction "P$3_3") (pintype "passive"))
      (node (ref "D5") (pin "P$1") (pinfunction "P$1_P$1") (pintype "bidirectional"))
      (node (ref "D5") (pin "P$11") (pinfunction "P$1_P$11") (pintype "bidirectional"))
      (node (ref "D6") (pin "P$1") (pinfunction "P$1_P$1") (pintype "bidirectional"))
      (node (ref "D6") (pin "P$11") (pinfunction "P$1_P$11") (pintype "bidirectional"))
      (node (ref "D7") (pin "P$1") (pinfunction "P$1_P$1") (pintype "bidirectional"))
      (node (ref "D7") (pin "P$11") (pinfunction "P$1_P$11") (pintype "bidirectional"))
      (node (ref "D8") (pin "P$1") (pinfunction "P$1_P$1") (pintype "bidirectional"))
      (node (ref "D8") (pin "P$11") (pinfunction "P$1_P$11") (pintype "bidirectional"))
      (node (ref "D9") (pin "P$1") (pinfunction "P$1_P$1") (pintype "bidirectional"))
      (node (ref "D9") (pin "P$11") (pinfunction "P$1_P$11") (pintype "bidirectional"))
      (node (ref "IC1") (pin "2") (pinfunction "GND_2") (pintype "power_in"))
      (node (ref "IC10") (pin "2") (pinfunction "GND_2") (pintype "bidirectional"))
      (node (ref "IC11") (pin "4") (pinfunction "GND_4") (pintype "power_in"))
      (node (ref "IC15") (pin "12") (pinfunction "GND2_12") (pintype "bidirectional"))
      (node (ref "IC15") (pin "13") (pinfunction "HEAT_13") (pintype "bidirectional"))
      (node (ref "IC15") (pin "6") (pinfunction "GND1_6") (pintype "bidirectional"))
      (node (ref "IC2") (pin "2") (pinfunction "GND_2") (pintype "power_in"))
      (node (ref "IC3") (pin "4") (pinfunction "G2A_4") (pintype "input"))
      (node (ref "IC3") (pin "5") (pinfunction "G2B_5") (pintype "input"))
      (node (ref "IC3") (pin "8") (pinfunction "GND_8") (pintype "power_in"))
      (node (ref "IC4") (pin "7") (pinfunction "VSS_7") (pintype "power_in"))
      (node (ref "IC5") (pin "15") (pinfunction "GND21_15") (pintype "bidirectional"))
      (node (ref "IC5") (pin "2") (pinfunction "GND11_2") (pintype "bidirectional"))
      (node (ref "IC5") (pin "8") (pinfunction "GND12_8") (pintype "bidirectional"))
      (node (ref "IC5") (pin "9") (pinfunction "GND22_9") (pintype "bidirectional"))
      (node (ref "IC6") (pin "12") (pinfunction "GND2_12") (pintype "bidirectional"))
      (node (ref "IC6") (pin "13") (pinfunction "HEAT_13") (pintype "bidirectional"))
      (node (ref "IC6") (pin "6") (pinfunction "GND1_6") (pintype "bidirectional"))
      (node (ref "IC7") (pin "12") (pinfunction "GND2_12") (pintype "bidirectional"))
      (node (ref "IC7") (pin "13") (pinfunction "HEAT_13") (pintype "bidirectional"))
      (node (ref "IC7") (pin "6") (pinfunction "GND1_6") (pintype "bidirectional"))
      (node (ref "IC8") (pin "2") (pinfunction "GND_2") (pintype "bidirectional"))
      (node (ref "IC9") (pin "2") (pinfunction "GND_2") (pintype "bidirectional"))
      (node (ref "PROZ1") (pin "47") (pinfunction "GND_47") (pintype "passive"))
      (node (ref "PROZ1") (pin "48") (pinfunction "GND_48") (pintype "passive"))
      (node (ref "Q1") (pin "2") (pinfunction "S_2") (pintype "passive"))
      (node (ref "Q12") (pin "2") (pinfunction "S_2") (pintype "passive"))
      (node (ref "Q13") (pin "2") (pinfunction "S_2") (pintype "passive"))
      (node (ref "Q2") (pin "2") (pinfunction "S_2") (pintype "passive"))
      (node (ref "Q3") (pin "2") (pinfunction "S_2") (pintype "passive"))
      (node (ref "Q4") (pin "2") (pinfunction "S_2") (pintype "passive"))
      (node (ref "R1") (pin "1") (pinfunction "1_1") (pintype "passive"))
      (node (ref "R11") (pin "1") (pinfunction "1_1") (pintype "passive"))
      (node (ref "R12") (pin "1") (pinfunction "1_1") (pintype "passive"))
      (node (ref "R14") (pin "1") (pinfunction "1_1") (pintype "passive"))
      (node (ref "R16") (pin "1") (pinfunction "1_1") (pintype "passive"))
      (node (ref "R17") (pin "1") (pinfunction "1_1") (pintype "passive"))
      (node (ref "R2") (pin "1") (pinfunction "1_1") (pintype "passive"))
      (node (ref "R20") (pin "1") (pinfunction "1_1") (pintype "passive"))
      (node (ref "R23") (pin "1") (pinfunction "1_1") (pintype "passive"))
      (node (ref "R27") (pin "2") (pinfunction "2_2") (pintype "passive"))
      (node (ref "R29") (pin "2") (pinfunction "2_2") (pintype "passive"))
      (node (ref "R3") (pin "1") (pinfunction "1_1") (pintype "passive"))
      (node (ref "R32") (pin "2") (pinfunction "2_2") (pintype "passive"))
      (node (ref "R34") (pin "2") (pinfunction "2_2") (pintype "passive"))
      (node (ref "R4") (pin "1") (pinfunction "1_1") (pintype "passive"))
      (node (ref "R50") (pin "1") (pinfunction "1_1") (pintype "passive"))
      (node (ref "R51") (pin "1") (pinfunction "1_1") (pintype "passive"))
      (node (ref "R52") (pin "1") (pinfunction "1_1") (pintype "passive"))
      (node (ref "R53") (pin "1") (pinfunction "1_1") (pintype "passive"))
      (node (ref "R54") (pin "1") (pinfunction "1_1") (pintype "passive"))
      (node (ref "R55") (pin "1") (pinfunction "1_1") (pintype "passive"))
      (node (ref "R56") (pin "2") (pinfunction "2_2") (pintype "passive"))
      (node (ref "R57") (pin "2") (pinfunction "2_2") (pintype "passive"))
      (node (ref "R58") (pin "2") (pinfunction "2_2") (pintype "passive"))
      (node (ref "R63") (pin "1") (pinfunction "1_1") (pintype "passive"))
      (node (ref "R77") (pin "1") (pinfunction "1_1") (pintype "passive"))
      (node (ref "R78") (pin "1") (pinfunction "1_1") (pintype "passive"))
      (node (ref "TB1") (pin "GND") (pinfunction "GND_GND") (pintype "power_in"))
      (node (ref "TB1") (pin "GND2") (pinfunction "GND_GND2") (pintype "power_in"))
      (node (ref "TERA-DC/DC1") (pin "GND@1") (pinfunction "GND_GND@1") (pintype "power_in"))
      (node (ref "TERA-DC/DC1") (pin "GND@2") (pinfunction "GND_GND@2") (pintype "power_in"))
      (node (ref "X1") (pin "1") (pinfunction "1_1") (pintype "passive"))
      (node (ref "X13") (pin "1") (pinfunction "1_1") (pintype "passive"))
      (node (ref "X14") (pin "1") (pinfunction "1_1") (pintype "passive"))
      (node (ref "X15") (pin "1") (pinfunction "1_1") (pintype "passive"))
      (node (ref "X2") (pin "1") (pinfunction "GND_1") (pintype "passive"))
      (node (ref "X20") (pin "P$1") (pinfunction "1_P$1") (pintype "bidirectional"))
      (node (ref "X3") (pin "1") (pinfunction "GND_1") (pintype "passive"))
      (node (ref "X4") (pin "1") (pinfunction "GND_1") (pintype "passive"))
    )
    (net (code "21") (name "HS_CO1") (class "Default")
      (node (ref "IC7") (pin "4") (pinfunction "CO1_4") (pintype "bidirectional"))
      (node (ref "PROZ1") (pin "36") (pinfunction "PB2_36") (pintype "bidirectional"))
    )
    (net (code "22") (name "HS_RM") (class "Default")
      (node (ref "PROZ1") (pin "37") (pinfunction "PB1_37") (pintype "bidirectional"))
      (node (ref "Q4") (pin "3") (pinfunction "D_3") (pintype "passive"))
      (node (ref "R21") (pin "1") (pinfunction "1_1") (pintype "passive"))
    )
    (net (code "23") (name "HS_RM_EX") (class "Default")
      (node (ref "R22") (pin "2") (pinfunction "2_2") (pintype "passive"))
      (node (ref "R23") (pin "2") (pinfunction "2_2") (pintype "passive"))
      (node (ref "X11") (pin "P$3") (pinfunction "3_P$3") (pintype "bidirectional"))
    )
    (net (code "24") (name "IL1") (class "Default")
      (node (ref "PROZ1") (pin "14") (pinfunction "PB6_14") (pintype "bidirectional"))
      (node (ref "Q1") (pin "1") (pinfunction "G_1") (pintype "passive"))
      (node (ref "R9") (pin "2") (pinfunction "2_2") (pintype "passive"))
    )
    (net (code "25") (name "IL2") (class "Default")
      (node (ref "PROZ1") (pin "12") (pinfunction "PB7_12") (pintype "bidirectional"))
      (node (ref "Q2") (pin "1") (pinfunction "G_1") (pintype "passive"))
      (node (ref "R13") (pin "2") (pinfunction "2_2") (pintype "passive"))
    )
    (net (code "26") (name "ILK1") (class "Default")
      (node (ref "IC4") (pin "11") (pinfunction "I0_11") (pintype "input"))
      (node (ref "JP4") (pin "2") (pinfunction "2_2") (pintype "passive"))
      (node (ref "Q1") (pin "3") (pinfunction "D_3") (pintype "passive"))
      (node (ref "X20") (pin "P$3") (pinfunction "3_P$3") (pintype "bidirectional"))
    )
    (net (code "27") (name "ILK2") (class "Default")
      (node (ref "IC4") (pin "12") (pinfunction "I1_12") (pintype "input"))
      (node (ref "IC4") (pin "13") (pinfunction "I2_13") (pintype "input"))
      (node (ref "JP3") (pin "2") (pinfunction "2_2") (pintype "passive"))
      (node (ref "Q2") (pin "3") (pinfunction "D_3") (pintype "passive"))
      (node (ref "X20") (pin "P$2") (pinfunction "2_P$2") (pintype "bidirectional"))
    )
    (net (code "28") (name "INTERLOCK_OK") (class "Default")
      (node (ref "IC15") (pin "1") (pinfunction "IN2_1") (pintype "bidirectional"))
      (node (ref "IC15") (pin "7") (pinfunction "IN1_7") (pintype "bidirectional"))
      (node (ref "IC4") (pin "10") (pinfunction "O_10") (pintype "output"))
      (node (ref "IC6") (pin "1") (pinfunction "IN2_1") (pintype "bidirectional"))
      (node (ref "IC6") (pin "7") (pinfunction "IN1_7") (pintype "bidirectional"))
      (node (ref "IC7") (pin "1") (pinfunction "IN2_1") (pintype "bidirectional"))
      (node (ref "IC7") (pin "7") (pinfunction "IN1_7") (pintype "bidirectional"))
      (node (ref "LED5") (pin "A") (pinfunction "A_A") (pintype "passive"))
      (node (ref "PROZ1") (pin "44") (pinfunction "PA3_44") (pintype "bidirectional"))
    )
    (net (code "29") (name "JTCK") (class "Default")
      (node (ref "PROZ1") (pin "18") (pinfunction "PA14_18") (pintype "bidirectional"))
      (node (ref "X2") (pin "5") (pinfunction "JTCK_5") (pintype "passive"))
    )
    (net (code "30") (name "JTDI") (class "Default")
      (node (ref "PROZ1") (pin "16") (pinfunction "PA15_16") (pintype "bidirectional"))
      (node (ref "X2") (pin "6") (pinfunction "JTDI_6") (pintype "passive"))
    )
    (net (code "31") (name "JTDO") (class "Default")
      (node (ref "PROZ1") (pin "20") (pinfunction "PB3_20") (pintype "bidirectional"))
      (node (ref "X2") (pin "7") (pinfunction "JTDO_7") (pintype "passive"))
    )
    (net (code "32") (name "JTMS") (class "Default")
      (node (ref "PROZ1") (pin "59") (pinfunction "PA13_59") (pintype "bidirectional"))
      (node (ref "X2") (pin "3") (pinfunction "JTMS_3") (pintype "passive"))
    )
    (net (code "33") (name "JTNRST") (class "Default")
      (node (ref "PROZ1") (pin "22") (pinfunction "PB4_22") (pintype "bidirectional"))
      (node (ref "X2") (pin "8") (pinfunction "JTNRST_8") (pintype "passive"))
    )
    (net (code "34") (name "LED1") (class "Default")
      (node (ref "PROZ1") (pin "25") (pinfunction "PB5_25") (pintype "bidirectional"))
    )
    (net (code "35") (name "LED2") (class "Default")
      (node (ref "PROZ1") (pin "27") (pinfunction "PD2_27") (pintype "bidirectional"))
    )
    (net (code "36") (name "LED3") (class "Default")
      (node (ref "PROZ1") (pin "29") (pinfunction "PC12_29") (pintype "bidirectional"))
    )
    (net (code "37") (name "LEM_1") (class "Default")
      (node (ref "C18") (pin "1") (pinfunction "1_1") (pintype "passive"))
      (node (ref "D7") (pin "P$2") (pinfunction "P$2_P$2") (pintype "bidirectional"))
      (node (ref "PROZ1") (pin "15") (pinfunction "PC0_15") (pintype "bidirectional"))
      (node (ref "R26") (pin "2") (pinfunction "2_2") (pintype "passive"))
    )
    (net (code "38") (name "LEM_2") (class "Default")
      (node (ref "C17") (pin "1") (pinfunction "1_1") (pintype "passive"))
      (node (ref "D6") (pin "P$2") (pinfunction "P$2_P$2") (pintype "bidirectional"))
      (node (ref "PROZ1") (pin "13") (pinfunction "PC1_13") (pintype "bidirectional"))
      (node (ref "R25") (pin "2") (pinfunction "2_2") (pintype "passive"))
    )
    (net (code "39") (name "LEM_3") (class "Default")
      (node (ref "C16") (pin "1") (pinfunction "1_1") (pintype "passive"))
      (node (ref "D8") (pin "P$2") (pinfunction "P$2_P$2") (pintype "bidirectional"))
      (node (ref "PROZ1") (pin "11") (pinfunction "PC2_11") (pintype "bidirectional"))
      (node (ref "R24") (pin "2") (pinfunction "2_2") (pintype "passive"))
    )
    (net (code "40") (name "MISO") (class "Default")
      (node (ref "CON1") (pin "7") (pinfunction "7_7") (pintype "passive"))
      (node (ref "IC15") (pin "11") (pinfunction "MISO/ST2_11") (pintype "bidirectional"))
      (node (ref "IC5") (pin "11") (pinfunction "IN_D_11") (pintype "bidirectional"))
      (node (ref "IC6") (pin "11") (pinfunction "MISO/ST2_11") (pintype "bidirectional"))
      (node (ref "IC7") (pin "11") (pinfunction "MISO/ST2_11") (pintype "bidirectional"))
    )
    (net (code "41") (name "MISO_M") (class "Default")
      (node (ref "IC5") (pin "6") (pinfunction "OUT_D_6") (pintype "bidirectional"))
      (node (ref "PROZ1") (pin "42") (pinfunction "PA6_42") (pintype "bidirectional"))
    )
    (net (code "42") (name "MOSI") (class "Default")
      (node (ref "CON1") (pin "6") (pinfunction "6_6") (pintype "passive"))
      (node (ref "IC15") (pin "2") (pinfunction "MOSI_2") (pintype "bidirectional"))
      (node (ref "IC5") (pin "13") (pinfunction "OUT_B_13") (pintype "bidirectional"))
      (node (ref "IC6") (pin "2") (pinfunction "MOSI_2") (pintype "bidirectional"))
      (node (ref "IC7") (pin "2") (pinfunction "MOSI_2") (pintype "bidirectional"))
    )
    (net (code "43") (name "MOSI_M") (class "Default")
      (node (ref "IC5") (pin "4") (pinfunction "IN_B_4") (pintype "bidirectional"))
      (node (ref "PROZ1") (pin "41") (pinfunction "PA7_41") (pintype "bidirectional"))
    )
    (net (code "44") (name "NALERT") (class "Default")
      (node (ref "IC4") (pin "9") (pinfunction "O_9") (pintype "output"))
      (node (ref "LED4") (pin "A") (pinfunction "A_A") (pintype "passive"))
      (node (ref "PROZ1") (pin "35") (pinfunction "PB10_35") (pintype "bidirectional"))
    )
    (net (code "45") (name "NALERT1") (class "Default")
      (node (ref "IC4") (pin "1") (pinfunction "I0_1") (pintype "input"))
      (node (ref "R50") (pin "2") (pinfunction "2_2") (pintype "passive"))
      (node (ref "X6") (pin "P$2") (pinfunction "2_P$2") (pintype "bidirectional"))
    )
    (net (code "46") (name "NALERT2") (class "Default")
      (node (ref "IC4") (pin "2") (pinfunction "I1_2") (pintype "input"))
      (node (ref "R51") (pin "2") (pinfunction "2_2") (pintype "passive"))
      (node (ref "X7") (pin "P$2") (pinfunction "2_P$2") (pintype "bidirectional"))
    )
    (net (code "47") (name "NALERT3") (class "Default")
      (node (ref "IC4") (pin "8") (pinfunction "I2_8") (pintype "input"))
      (node (ref "R52") (pin "2") (pinfunction "2_2") (pintype "passive"))
      (node (ref "X8") (pin "P$2") (pinfunction "2_P$2") (pintype "bidirectional"))
    )
    (net (code "48") (name "NCS1") (class "Default")
      (node (ref "CON1") (pin "5") (pinfunction "5_5") (pintype "passive"))
      (node (ref "IC3") (pin "15") (pinfunction "Y0_15") (pintype "output"))
    )
    (net (code "49") (name "NCS2") (class "Default")
      (node (ref "CON1") (pin "4") (pinfunction "4_4") (pintype "passive"))
      (node (ref "IC3") (pin "14") (pinfunction "Y1_14") (pintype "output"))
    )
    (net (code "50") (name "NCS3") (class "Default")
      (node (ref "CON1") (pin "3") (pinfunction "3_3") (pintype "passive"))
      (node (ref "IC3") (pin "13") (pinfunction "Y2_13") (pintype "output"))
    )
    (net (code "51") (name "NCS4") (class "Default")
      (node (ref "CON1") (pin "2") (pinfunction "2_2") (pintype "passive"))
      (node (ref "IC3") (pin "12") (pinfunction "Y3_12") (pintype "output"))
    )
    (net (code "52") (name "NCS5") (class "Default")
      (node (ref "IC3") (pin "11") (pinfunction "Y4_11") (pintype "output"))
    )
    (net (code "53") (name "NCS6") (class "Default")
      (node (ref "IC3") (pin "10") (pinfunction "Y5_10") (pintype "output"))
      (node (ref "IC7") (pin "8") (pinfunction "NCS_8") (pintype "bidirectional"))
    )
    (net (code "54") (name "NCS7") (class "Default")
      (node (ref "IC3") (pin "9") (pinfunction "Y6_9") (pintype "output"))
      (node (ref "IC6") (pin "8") (pinfunction "NCS_8") (pintype "bidirectional"))
    )
    (net (code "55") (name "NCS8") (class "Default")
      (node (ref "IC15") (pin "8") (pinfunction "NCS_8") (pintype "bidirectional"))
      (node (ref "IC3") (pin "7") (pinfunction "Y7_7") (pintype "output"))
    )
    (net (code "56") (name "NFAULT") (class "Default")
      (node (ref "IC4") (pin "6") (pinfunction "O_6") (pintype "output"))
      (node (ref "LED3") (pin "A") (pinfunction "A_A") (pintype "passive"))
      (node (ref "PROZ1") (pin "53") (pinfunction "PC7_53") (pintype "bidirectional"))
    )
    (net (code "57") (name "NFAULT1") (class "Default")
      (node (ref "IC4") (pin "3") (pinfunction "I0_3") (pintype "input"))
      (node (ref "R53") (pin "2") (pinfunction "2_2") (pintype "passive"))
      (node (ref "X6") (pin "P$1") (pinfunction "1_P$1") (pintype "bidirectional"))
    )
    (net (code "58") (name "NFAULT2") (class "Default")
      (node (ref "IC4") (pin "4") (pinfunction "I1_4") (pintype "input"))
      (node (ref "R54") (pin "2") (pinfunction "2_2") (pintype "passive"))
      (node (ref "X7") (pin "P$1") (pinfunction "1_P$1") (pintype "bidirectional"))
    )
    (net (code "59") (name "NFAULT3") (class "Default")
      (node (ref "IC4") (pin "5") (pinfunction "I2_5") (pintype "input"))
      (node (ref "R55") (pin "2") (pinfunction "2_2") (pintype "passive"))
      (node (ref "X8") (pin "P$1") (pinfunction "1_P$1") (pintype "bidirectional"))
    )
    (net (code "60") (name "NRST") (class "Default")
      (node (ref "PROZ1") (pin "17") (pinfunction "NRST_17") (pintype "bidirectional"))
      (node (ref "X2") (pin "4") (pinfunction "NRST_4") (pintype "passive"))
    )
    (net (code "61") (name "Net-(C4-Pad1)") (class "Default")
      (node (ref "C4") (pin "1") (pinfunction "1_1") (pintype "passive"))
      (node (ref "R5") (pin "1") (pinfunction "1_1") (pintype "passive"))
      (node (ref "R6") (pin "1") (pinfunction "1_1") (pintype "passive"))
    )
    (net (code "62") (name "Net-(C5-Pad1)") (class "Default")
      (node (ref "C5") (pin "1") (pinfunction "1_1") (pintype "passive"))
      (node (ref "R7") (pin "1") (pinfunction "1_1") (pintype "passive"))
      (node (ref "R8") (pin "1") (pinfunction "1_1") (pintype "passive"))
    )
    (net (code "63") (name "Net-(CON2-Pad1)") (class "Default")
      (node (ref "CON2") (pin "1") (pinfunction "1_1") (pintype "passive"))
      (node (ref "R30") (pin "1") (pinfunction "1_1") (pintype "passive"))
    )
    (net (code "64") (name "Net-(CON3-Pad1)") (class "Default")
      (node (ref "CON3") (pin "1") (pinfunction "1_1") (pintype "passive"))
      (node (ref "R28") (pin "1") (pinfunction "1_1") (pintype "passive"))
    )
    (net (code "65") (name "Net-(CON4-Pad1)") (class "Default")
      (node (ref "CON4") (pin "1") (pinfunction "1_1") (pintype "passive"))
      (node (ref "R31") (pin "1") (pinfunction "1_1") (pintype "passive"))
    )
    (net (code "66") (name "Net-(CON5-Pad1)") (class "Default")
      (node (ref "CON5") (pin "1") (pinfunction "1_1") (pintype "passive"))
      (node (ref "R33") (pin "1") (pinfunction "1_1") (pintype "passive"))
    )
    (net (code "67") (name "Net-(IC1-RS)") (class "Default")
      (node (ref "IC1") (pin "8") (pinfunction "RS_8") (pintype "passive"))
      (node (ref "R3") (pin "2") (pinfunction "2_2") (pintype "passive"))
    )
    (net (code "68") (name "Net-(IC2-RS)") (class "Default")
      (node (ref "IC2") (pin "8") (pinfunction "RS_8") (pintype "passive"))
      (node (ref "R4") (pin "2") (pinfunction "2_2") (pintype "passive"))
    )
    (net (code "69") (name "Net-(IC2-VCC)") (class "Default")
      (node (ref "C2") (pin "1") (pinfunction "1_1") (pintype "passive"))
      (node (ref "IC2") (pin "3") (pinfunction "VCC_3") (pintype "power_in"))
      (node (ref "J3") (pin "P$2") (pinfunction "P$2_P$2") (pintype "bidirectional"))
    )
    (net (code "70") (name "Net-(IC6-OUT1)") (class "Default")
      (node (ref "IC6") (pin "9") (pinfunction "OUT1_9") (pintype "bidirectional"))
      (node (ref "R61") (pin "1") (pinfunction "1_1") (pintype "passive"))
      (node (ref "X10") (pin "P$1") (pinfunction "1_P$1") (pintype "bidirectional"))
    )
    (net (code "71") (name "Net-(IC6-OUT2)") (class "Default")
      (node (ref "IC6") (pin "3") (pinfunction "OUT2_3") (pintype "bidirectional"))
      (node (ref "R62") (pin "1") (pinfunction "1_1") (pintype "passive"))
      (node (ref "X9") (pin "P$1") (pinfunction "1_P$1") (pintype "bidirectional"))
    )
    (net (code "72") (name "Net-(IC7-OUT1)") (class "Default")
      (node (ref "IC7") (pin "9") (pinfunction "OUT1_9") (pintype "bidirectional"))
      (node (ref "R59") (pin "1") (pinfunction "1_1") (pintype "passive"))
      (node (ref "X12") (pin "P$1") (pinfunction "1_P$1") (pintype "bidirectional"))
    )
    (net (code "73") (name "Net-(IC7-OUT2)") (class "Default")
      (node (ref "IC7") (pin "3") (pinfunction "OUT2_3") (pintype "bidirectional"))
      (node (ref "R60") (pin "1") (pinfunction "1_1") (pintype "passive"))
      (node (ref "X11") (pin "P$1") (pinfunction "1_P$1") (pintype "bidirectional"))
    )
    (net (code "74") (name "Net-(IC8-VREF)") (class "Default")
      (node (ref "C13") (pin "1") (pinfunction "1_1") (pintype "passive"))
      (node (ref "IC8") (pin "5") (pinfunction "VREF_5") (pintype "bidirectional"))
      (node (ref "R58") (pin "1") (pinfunction "1_1") (pintype "passive"))
      (node (ref "X13") (pin "3") (pinfunction "3_3") (pintype "passive"))
    )
    (net (code "75") (name "Net-(IC9-VREF)") (class "Default")
      (node (ref "C14") (pin "1") (pinfunction "1_1") (pintype "passive"))
      (node (ref "IC9") (pin "5") (pinfunction "VREF_5") (pintype "bidirectional"))
      (node (ref "R57") (pin "1") (pinfunction "1_1") (pintype "passive"))
      (node (ref "X14") (pin "3") (pinfunction "3_3") (pintype "passive"))
    )
    (net (code "76") (name "Net-(IC10-VREF)") (class "Default")
      (node (ref "C15") (pin "1") (pinfunction "1_1") (pintype "passive"))
      (node (ref "IC10") (pin "5") (pinfunction "VREF_5") (pintype "bidirectional"))
      (node (ref "R56") (pin "1") (pinfunction "1_1") (pintype "passive"))
      (node (ref "X15") (pin "3") (pinfunction "3_3") (pintype "passive"))
    )
    (net (code "77") (name "Net-(IC15-OUT1)") (class "Default")
      (node (ref "IC15") (pin "9") (pinfunction "OUT1_9") (pintype "bidirectional"))
      (node (ref "R71") (pin "1") (pinfunction "1_1") (pintype "passive"))
      (node (ref "X21") (pin "P$1") (pinfunction "1_P$1") (pintype "bidirectional"))
    )
    (net (code "78") (name "Net-(IC15-OUT2)") (class "Default")
      (node (ref "IC15") (pin "3") (pinfunction "OUT2_3") (pintype "bidirectional"))
      (node (ref "R72") (pin "1") (pinfunction "1_1") (pintype "passive"))
      (node (ref "X22") (pin "P$1") (pinfunction "1_P$1") (pintype "bidirectional"))
    )
    (net (code "79") (name "Net-(JP3-Pad1)") (class "Default")
      (node (ref "JP3") (pin "1") (pinfunction "1_1") (pintype "passive"))
      (node (ref "R15") (pin "1") (pinfunction "1_1") (pintype "passive"))
    )
    (net (code "80") (name "Net-(JP3-Pad3)") (class "Default")
      (node (ref "JP3") (pin "3") (pinfunction "3_3") (pintype "passive"))
      (node (ref "R16") (pin "2") (pinfunction "2_2") (pintype "passive"))
    )
    (net (code "81") (name "Net-(JP4-Pad1)") (class "Default")
      (node (ref "JP4") (pin "1") (pinfunction "1_1") (pintype "passive"))
      (node (ref "R10") (pin "1") (pinfunction "1_1") (pintype "passive"))
    )
    (net (code "82") (name "Net-(JP4-Pad3)") (class "Default")
      (node (ref "JP4") (pin "3") (pinfunction "3_3") (pintype "passive"))
      (node (ref "R11") (pin "2") (pinfunction "2_2") (pintype "passive"))
    )
    (net (code "83") (name "Net-(LED1-PadC)") (class "Default")
      (node (ref "LED1") (pin "C") (pinfunction "C_C") (pintype "passive"))
      (node (ref "R1") (pin "2") (pinfunction "2_2") (pintype "passive"))
    )
    (net (code "84") (name "Net-(LED2-PadC)") (class "Default")
      (node (ref "LED2") (pin "C") (pinfunction "C_C") (pintype "passive"))
      (node (ref "R2") (pin "2") (pinfunction "2_2") (pintype "passive"))
    )
    (net (code "85") (name "Net-(LED3-PadC)") (class "Default")
      (node (ref "LED3") (pin "C") (pinfunction "C_C") (pintype "passive"))
      (node (ref "R12") (pin "2") (pinfunction "2_2") (pintype "passive"))
    )
    (net (code "86") (name "Net-(LED4-PadC)") (class "Default")
      (node (ref "LED4") (pin "C") (pinfunction "C_C") (pintype "passive"))
      (node (ref "R14") (pin "2") (pinfunction "2_2") (pintype "passive"))
    )
    (net (code "87") (name "Net-(LED5-PadC)") (class "Default")
      (node (ref "LED5") (pin "C") (pinfunction "C_C") (pintype "passive"))
      (node (ref "R17") (pin "2") (pinfunction "2_2") (pintype "passive"))
    )
    (net (code "88") (name "Net-(LED6-PadC)") (class "Default")
      (node (ref "LED6") (pin "C") (pinfunction "C_C") (pintype "passive"))
      (node (ref "R59") (pin "2") (pinfunction "2_2") (pintype "passive"))
    )
    (net (code "89") (name "Net-(LED7-PadC)") (class "Default")
      (node (ref "LED7") (pin "C") (pinfunction "C_C") (pintype "passive"))
      (node (ref "R60") (pin "2") (pinfunction "2_2") (pintype "passive"))
    )
    (net (code "90") (name "Net-(LED8-PadC)") (class "Default")
      (node (ref "LED8") (pin "C") (pinfunction "C_C") (pintype "passive"))
      (node (ref "R61") (pin "2") (pinfunction "2_2") (pintype "passive"))
    )
    (net (code "91") (name "Net-(LED9-PadC)") (class "Default")
      (node (ref "LED9") (pin "C") (pinfunction "C_C") (pintype "passive"))
      (node (ref "R62") (pin "2") (pinfunction "2_2") (pintype "passive"))
    )
    (net (code "92") (name "Net-(LED10-PadC)") (class "Default")
      (node (ref "LED10") (pin "C") (pinfunction "C_C") (pintype "passive"))
      (node (ref "R63") (pin "2") (pinfunction "2_2") (pintype "passive"))
    )
    (net (code "93") (name "Net-(LED12-PadC)") (class "Default")
      (node (ref "LED12") (pin "C") (pinfunction "C_C") (pintype "passive"))
      (node (ref "R71") (pin "2") (pinfunction "2_2") (pintype "passive"))
    )
    (net (code "94") (name "Net-(LED13-PadC)") (class "Default")
      (node (ref "LED13") (pin "C") (pinfunction "C_C") (pintype "passive"))
      (node (ref "R72") (pin "2") (pinfunction "2_2") (pintype "passive"))
    )
    (net (code "95") (name "Net-(Q3-G)") (class "Default")
      (node (ref "Q3") (pin "1") (pinfunction "G_1") (pintype "passive"))
      (node (ref "R19") (pin "1") (pinfunction "1_1") (pintype "passive"))
    )
    (net (code "96") (name "Net-(Q4-G)") (class "Default")
      (node (ref "Q4") (pin "1") (pinfunction "G_1") (pintype "passive"))
      (node (ref "R22") (pin "1") (pinfunction "1_1") (pintype "passive"))
    )
    (net (code "97") (name "Net-(Q12-G)") (class "Default")
      (node (ref "Q12") (pin "1") (pinfunction "G_1") (pintype "passive"))
      (node (ref "R76") (pin "1") (pinfunction "1_1") (pintype "passive"))
    )
    (net (code "98") (name "Net-(Q13-G)") (class "Default")
      (node (ref "Q13") (pin "1") (pinfunction "G_1") (pintype "passive"))
      (node (ref "R74") (pin "1") (pinfunction "1_1") (pintype "passive"))
    )
    (net (code "99") (name "Net-(R5-Pad2)") (class "Default")
      (node (ref "R5") (pin "2") (pinfunction "2_2") (pintype "passive"))
      (node (ref "SW2") (pin "3") (pinfunction "3_3") (pintype "passive"))
    )
    (net (code "100") (name "Net-(R6-Pad2)") (class "Default")
      (node (ref "R6") (pin "2") (pinfunction "2_2") (pintype "passive"))
      (node (ref "SW2") (pin "4") (pinfunction "4_4") (pintype "passive"))
    )
    (net (code "101") (name "Net-(R7-Pad2)") (class "Default")
      (node (ref "R7") (pin "2") (pinfunction "2_2") (pintype "passive"))
      (node (ref "SW1") (pin "4") (pinfunction "4_4") (pintype "passive"))
    )
    (net (code "102") (name "Net-(R8-Pad2)") (class "Default")
      (node (ref "R8") (pin "2") (pinfunction "2_2") (pintype "passive"))
      (node (ref "SW1") (pin "3") (pinfunction "3_3") (pintype "passive"))
    )
    (net (code "103") (name "Net-(R24-Pad1)") (class "Default")
      (node (ref "R24") (pin "1") (pinfunction "1_1") (pintype "passive"))
      (node (ref "X13") (pin "2") (pinfunction "2_2") (pintype "passive"))
    )
    (net (code "104") (name "Net-(R25-Pad1)") (class "Default")
      (node (ref "R25") (pin "1") (pinfunction "1_1") (pintype "passive"))
      (node (ref "X14") (pin "2") (pinfunction "2_2") (pintype "passive"))
    )
    (net (code "105") (name "Net-(R26-Pad1)") (class "Default")
      (node (ref "R26") (pin "1") (pinfunction "1_1") (pintype "passive"))
      (node (ref "X15") (pin "2") (pinfunction "2_2") (pintype "passive"))
    )
    (net (code "106") (name "Net-(X10-3)") (class "Default")
      (node (ref "X10") (pin "P$3") (pinfunction "3_P$3") (pintype "bidirectional"))
      (node (ref "X9") (pin "P$4") (pinfunction "4_P$4") (pintype "bidirectional"))
    )
    (net (code "107") (name "Net-(X11-4)") (class "Default")
      (node (ref "X11") (pin "P$4") (pinfunction "4_P$4") (pintype "bidirectional"))
      (node (ref "X12") (pin "P$3") (pinfunction "3_P$3") (pintype "bidirectional"))
    )
    (net (code "108") (name "PA0") (class "Default")
      (node (ref "PROZ1") (pin "7") (pinfunction "PA0_7") (pintype "bidirectional"))
    )
    (net (code "109") (name "PA10") (class "Default")
      (node (ref "PROZ1") (pin "58") (pinfunction "PA10_58") (pintype "bidirectional"))
    )
    (net (code "110") (name "PB8") (class "Default")
      (node (ref "PROZ1") (pin "10") (pinfunction "PB8_10") (pintype "bidirectional"))
    )
    (net (code "111") (name "PB9") (class "Default")
      (node (ref "PROZ1") (pin "8") (pinfunction "PB9_8") (pintype "bidirectional"))
    )
    (net (code "112") (name "PC3") (class "Default")
      (node (ref "PROZ1") (pin "9") (pinfunction "PC3_9") (pintype "bidirectional"))
    )
    (net (code "113") (name "PC9") (class "Default")
      (node (ref "PROZ1") (pin "55") (pinfunction "PC9_55") (pintype "bidirectional"))
    )
    (net (code "114") (name "PC13") (class "Default")
      (node (ref "PROZ1") (pin "23") (pinfunction "PC13_23") (pintype "bidirectional"))
    )
    (net (code "115") (name "PC14") (class "Default")
      (node (ref "PROZ1") (pin "21") (pinfunction "PC14_21") (pintype "bidirectional"))
    )
    (net (code "116") (name "PC15") (class "Default")
      (node (ref "PROZ1") (pin "19") (pinfunction "PC15_19") (pintype "bidirectional"))
    )
    (net (code "117") (name "RM_KVL1") (class "Default")
      (node (ref "PROZ1") (pin "33") (pinfunction "PB14_33") (pintype "bidirectional"))
      (node (ref "Q13") (pin "3") (pinfunction "D_3") (pintype "passive"))
      (node (ref "R73") (pin "1") (pinfunction "1_1") (pintype "passive"))
    )
    (net (code "118") (name "RM_KVL1_EX") (class "Default")
      (node (ref "R74") (pin "2") (pinfunction "2_2") (pintype "passive"))
      (node (ref "R77") (pin "2") (pinfunction "2_2") (pintype "passive"))
      (node (ref "X21") (pin "P$3") (pinfunction "3_P$3") (pintype "bidirectional"))
    )
    (net (code "119") (name "RM_KVL2") (class "Default")
      (node (ref "PROZ1") (pin "34") (pinfunction "PB11_34") (pintype "bidirectional"))
      (node (ref "Q12") (pin "3") (pinfunction "D_3") (pintype "passive"))
      (node (ref "R75") (pin "1") (pinfunction "1_1") (pintype "passive"))
    )
    (net (code "120") (name "RM_KVL2_EX") (class "Default")
      (node (ref "R76") (pin "2") (pinfunction "2_2") (pintype "passive"))
      (node (ref "R78") (pin "2") (pinfunction "2_2") (pintype "passive"))
      (node (ref "X22") (pin "P$3") (pinfunction "3_P$3") (pintype "bidirectional"))
    )
    (net (code "121") (name "SCLK") (class "Default")
      (node (ref "CON1") (pin "8") (pinfunction "8_8") (pintype "passive"))
      (node (ref "IC15") (pin "5") (pinfunction "SCLK_5") (pintype "bidirectional"))
      (node (ref "IC5") (pin "14") (pinfunction "OUT_A_14") (pintype "bidirectional"))
      (node (ref "IC6") (pin "5") (pinfunction "SCLK_5") (pintype "bidirectional"))
      (node (ref "IC7") (pin "5") (pinfunction "SCLK_5") (pintype "bidirectional"))
    )
    (net (code "122") (name "SCLK_M") (class "Default")
      (node (ref "IC5") (pin "3") (pinfunction "IN_A_3") (pintype "bidirectional"))
      (node (ref "PROZ1") (pin "60") (pinfunction "PA5_60") (pintype "bidirectional"))
    )
    (net (code "123") (name "SLS_CO1") (class "Default")
      (node (ref "IC6") (pin "4") (pinfunction "CO1_4") (pintype "bidirectional"))
      (node (ref "PROZ1") (pin "57") (pinfunction "PA9_57") (pintype "bidirectional"))
    )
    (net (code "124") (name "SLS_RM") (class "Default")
      (node (ref "PROZ1") (pin "56") (pinfunction "PA8_56") (pintype "bidirectional"))
      (node (ref "Q3") (pin "3") (pinfunction "D_3") (pintype "passive"))
      (node (ref "R18") (pin "1") (pinfunction "1_1") (pintype "passive"))
    )
    (net (code "125") (name "SLS_RM_EX") (class "Default")
      (node (ref "R19") (pin "2") (pinfunction "2_2") (pintype "passive"))
      (node (ref "R20") (pin "2") (pinfunction "2_2") (pintype "passive"))
      (node (ref "X9") (pin "P$3") (pinfunction "3_P$3") (pintype "bidirectional"))
    )
    (net (code "126") (name "SPI_CS") (class "Default")
      (node (ref "IC3") (pin "6") (pinfunction "G1_6") (pintype "input"))
      (node (ref "PROZ1") (pin "38") (pinfunction "PB0_38") (pintype "bidirectional"))
    )
    (net (code "127") (name "TS1") (class "Default")
      (node (ref "C21") (pin "2") (pinfunction "2_2") (pintype "passive"))
      (node (ref "D9") (pin "P$2") (pinfunction "P$2_P$2") (pintype "bidirectional"))
      (node (ref "PROZ1") (pin "40") (pinfunction "PC4_40") (pintype "bidirectional"))
      (node (ref "R29") (pin "1") (pinfunction "1_1") (pintype "passive"))
      (node (ref "R30") (pin "2") (pinfunction "2_2") (pintype "passive"))
    )
    (net (code "128") (name "TS2") (class "Default")
      (node (ref "C20") (pin "2") (pinfunction "2_2") (pintype "passive"))
      (node (ref "D10") (pin "P$2") (pinfunction "P$2_P$2") (pintype "bidirectional"))
      (node (ref "PROZ1") (pin "39") (pinfunction "PC5_39") (pintype "bidirectional"))
      (node (ref "R27") (pin "1") (pinfunction "1_1") (pintype "passive"))
      (node (ref "R28") (pin "2") (pinfunction "2_2") (pintype "passive"))
    )
    (net (code "129") (name "TS3") (class "Default")
      (node (ref "C25") (pin "2") (pinfunction "2_2") (pintype "passive"))
      (node (ref "D1") (pin "P$2") (pinfunction "P$2_P$2") (pintype "bidirectional"))
      (node (ref "PROZ1") (pin "5") (pinfunction "PA1_5") (pintype "bidirectional"))
      (node (ref "R31") (pin "2") (pinfunction "2_2") (pintype "passive"))
      (node (ref "R32") (pin "1") (pinfunction "1_1") (pintype "passive"))
    )
    (net (code "130") (name "TS4") (class "Default")
      (node (ref "C26") (pin "2") (pinfunction "2_2") (pintype "passive"))
      (node (ref "D11") (pin "P$2") (pinfunction "P$2_P$2") (pintype "bidirectional"))
      (node (ref "PROZ1") (pin "3") (pinfunction "PA2_3") (pintype "bidirectional"))
      (node (ref "R33") (pin "2") (pinfunction "2_2") (pintype "passive"))
      (node (ref "R34") (pin "1") (pinfunction "1_1") (pintype "passive"))
    )
    (net (code "131") (name "USART_RXD") (class "Default")
      (node (ref "PROZ1") (pin "30") (pinfunction "PC11_30") (pintype "bidirectional"))
      (node (ref "X2") (pin "10") (pinfunction "RXD_10") (pintype "passive"))
    )
    (net (code "132") (name "USART_TXD") (class "Default")
      (node (ref "PROZ1") (pin "28") (pinfunction "PC10_28") (pintype "bidirectional"))
      (node (ref "X2") (pin "9") (pinfunction "TXD_9") (pintype "passive"))
    )
    (net (code "133") (name "VBAT") (class "Default")
      (node (ref "C19") (pin "1") (pinfunction "1_1") (pintype "passive"))
      (node (ref "D2") (pin "C") (pinfunction "C_C") (pintype "passive"))
      (node (ref "IC11") (pin "2") (pinfunction "VIN_2") (pintype "passive"))
      (node (ref "LED10") (pin "A") (pinfunction "A_A") (pintype "passive"))
      (node (ref "LED12") (pin "A") (pinfunction "A_A") (pintype "passive"))
      (node (ref "LED13") (pin "A") (pinfunction "A_A") (pintype "passive"))
      (node (ref "LED6") (pin "A") (pinfunction "A_A") (pintype "passive"))
      (node (ref "LED7") (pin "A") (pinfunction "A_A") (pintype "passive"))
      (node (ref "LED8") (pin "A") (pinfunction "A_A") (pintype "passive"))
      (node (ref "LED9") (pin "A") (pinfunction "A_A") (pintype "passive"))
      (node (ref "TB1") (pin "VIN") (pinfunction "VIN_VIN") (pintype "passive"))
      (node (ref "TERA-DC/DC1") (pin "VIN") (pinfunction "VIN_VIN") (pintype "passive"))
      (node (ref "X1") (pin "2") (pinfunction "2_2") (pintype "passive"))
      (node (ref "X10") (pin "P$2") (pinfunction "2_P$2") (pintype "bidirectional"))
      (node (ref "X10") (pin "P$4") (pinfunction "4_P$4") (pintype "bidirectional"))
      (node (ref "X11") (pin "P$2") (pinfunction "2_P$2") (pintype "bidirectional"))
      (node (ref "X12") (pin "P$2") (pinfunction "2_P$2") (pintype "bidirectional"))
      (node (ref "X12") (pin "P$4") (pinfunction "4_P$4") (pintype "bidirectional"))
      (node (ref "X21") (pin "P$2") (pinfunction "2_P$2") (pintype "bidirectional"))
      (node (ref "X21") (pin "P$4") (pinfunction "4_P$4") (pintype "bidirectional"))
      (node (ref "X22") (pin "P$2") (pinfunction "2_P$2") (pintype "bidirectional"))
      (node (ref "X22") (pin "P$4") (pinfunction "4_P$4") (pintype "bidirectional"))
      (node (ref "X3") (pin "4") (pinfunction "V+_4") (pintype "passive"))
      (node (ref "X4") (pin "4") (pinfunction "V+_4") (pintype "passive"))
      (node (ref "X9") (pin "P$2") (pinfunction "2_P$2") (pintype "bidirectional"))
    )
    (net (code "134") (name "VL_CO1") (class "Default")
      (node (ref "IC15") (pin "4") (pinfunction "CO1_4") (pintype "bidirectional"))
      (node (ref "PROZ1") (pin "54") (pinfunction "PC8_54") (pintype "bidirectional"))
    )
    (net (code "135") (name "VREF_PTC_CH") (class "Default")
      (node (ref "C20") (pin "1") (pinfunction "1_1") (pintype "passive"))
      (node (ref "C21") (pin "1") (pinfunction "1_1") (pintype "passive"))
      (node (ref "C22") (pin "1") (pinfunction "1_1") (pintype "passive"))
      (node (ref "C25") (pin "1") (pinfunction "1_1") (pintype "passive"))
      (node (ref "C26") (pin "1") (pinfunction "1_1") (pintype "passive"))
      (node (ref "CON2") (pin "2") (pinfunction "2_2") (pintype "passive"))
      (node (ref "CON3") (pin "2") (pinfunction "2_2") (pintype "passive"))
      (node (ref "CON4") (pin "2") (pinfunction "2_2") (pintype "passive"))
      (node (ref "CON5") (pin "2") (pinfunction "2_2") (pintype "passive"))
      (node (ref "IC11") (pin "6") (pinfunction "VOUT_6") (pintype "bidirectional"))
    )
    (net (code "136") (name "unconnected-(IC1-VREF-Pad5)") (class "Default")
      (node (ref "IC1") (pin "5") (pinfunction "VREF_5") (pintype "passive"))
    )
    (net (code "137") (name "unconnected-(IC2-VREF-Pad5)") (class "Default")
      (node (ref "IC2") (pin "5") (pinfunction "VREF_5") (pintype "passive"))
    )
    (net (code "138") (name "unconnected-(IC5-IN_C-Pad5)") (class "Default")
      (node (ref "IC5") (pin "5") (pinfunction "IN_C_5") (pintype "bidirectional"))
    )
    (net (code "139") (name "unconnected-(IC5-OUT_C-Pad12)") (class "Default")
      (node (ref "IC5") (pin "12") (pinfunction "OUT_C_12") (pintype "bidirectional"))
    )
    (net (code "140") (name "unconnected-(IC11-~{SHDN}-Pad3)") (class "Default")
      (node (ref "IC11") (pin "3") (pinfunction "~{SHDN}_3") (pintype "passive"))
    )
    (net (code "141") (name "unconnected-(J3-PadP$3)") (class "Default")
      (node (ref "J3") (pin "P$3") (pinfunction "P$3_P$3") (pintype "bidirectional"))
    )
    (net (code "142") (name "unconnected-(PROZ1F-AGND-Pad1)") (class "Default")
      (node (ref "PROZ1") (pin "1") (pinfunction "AGND_1") (pintype "passive"))
    )
    (net (code "143") (name "unconnected-(PROZ1F-VBAT-Pad6)") (class "Default")
      (node (ref "PROZ1") (pin "6") (pinfunction "VBAT_6") (pintype "passive"))
    )
    (net (code "144") (name "unconnected-(PROZ1F-VDDA_IN-Pad2)") (class "Default")
      (node (ref "PROZ1") (pin "2") (pinfunction "VDDA_IN_2") (pintype "passive"))
    )
    (net (code "145") (name "unconnected-(PROZ1F-VDDA_OUT-Pad4)") (class "Default")
      (node (ref "PROZ1") (pin "4") (pinfunction "VDDA_OUT_4") (pintype "passive"))
    )
  )
)
